# haasoscope_pro_power_board_-_5V.net
KiCad netlist of a schematic drawn in EAGLE
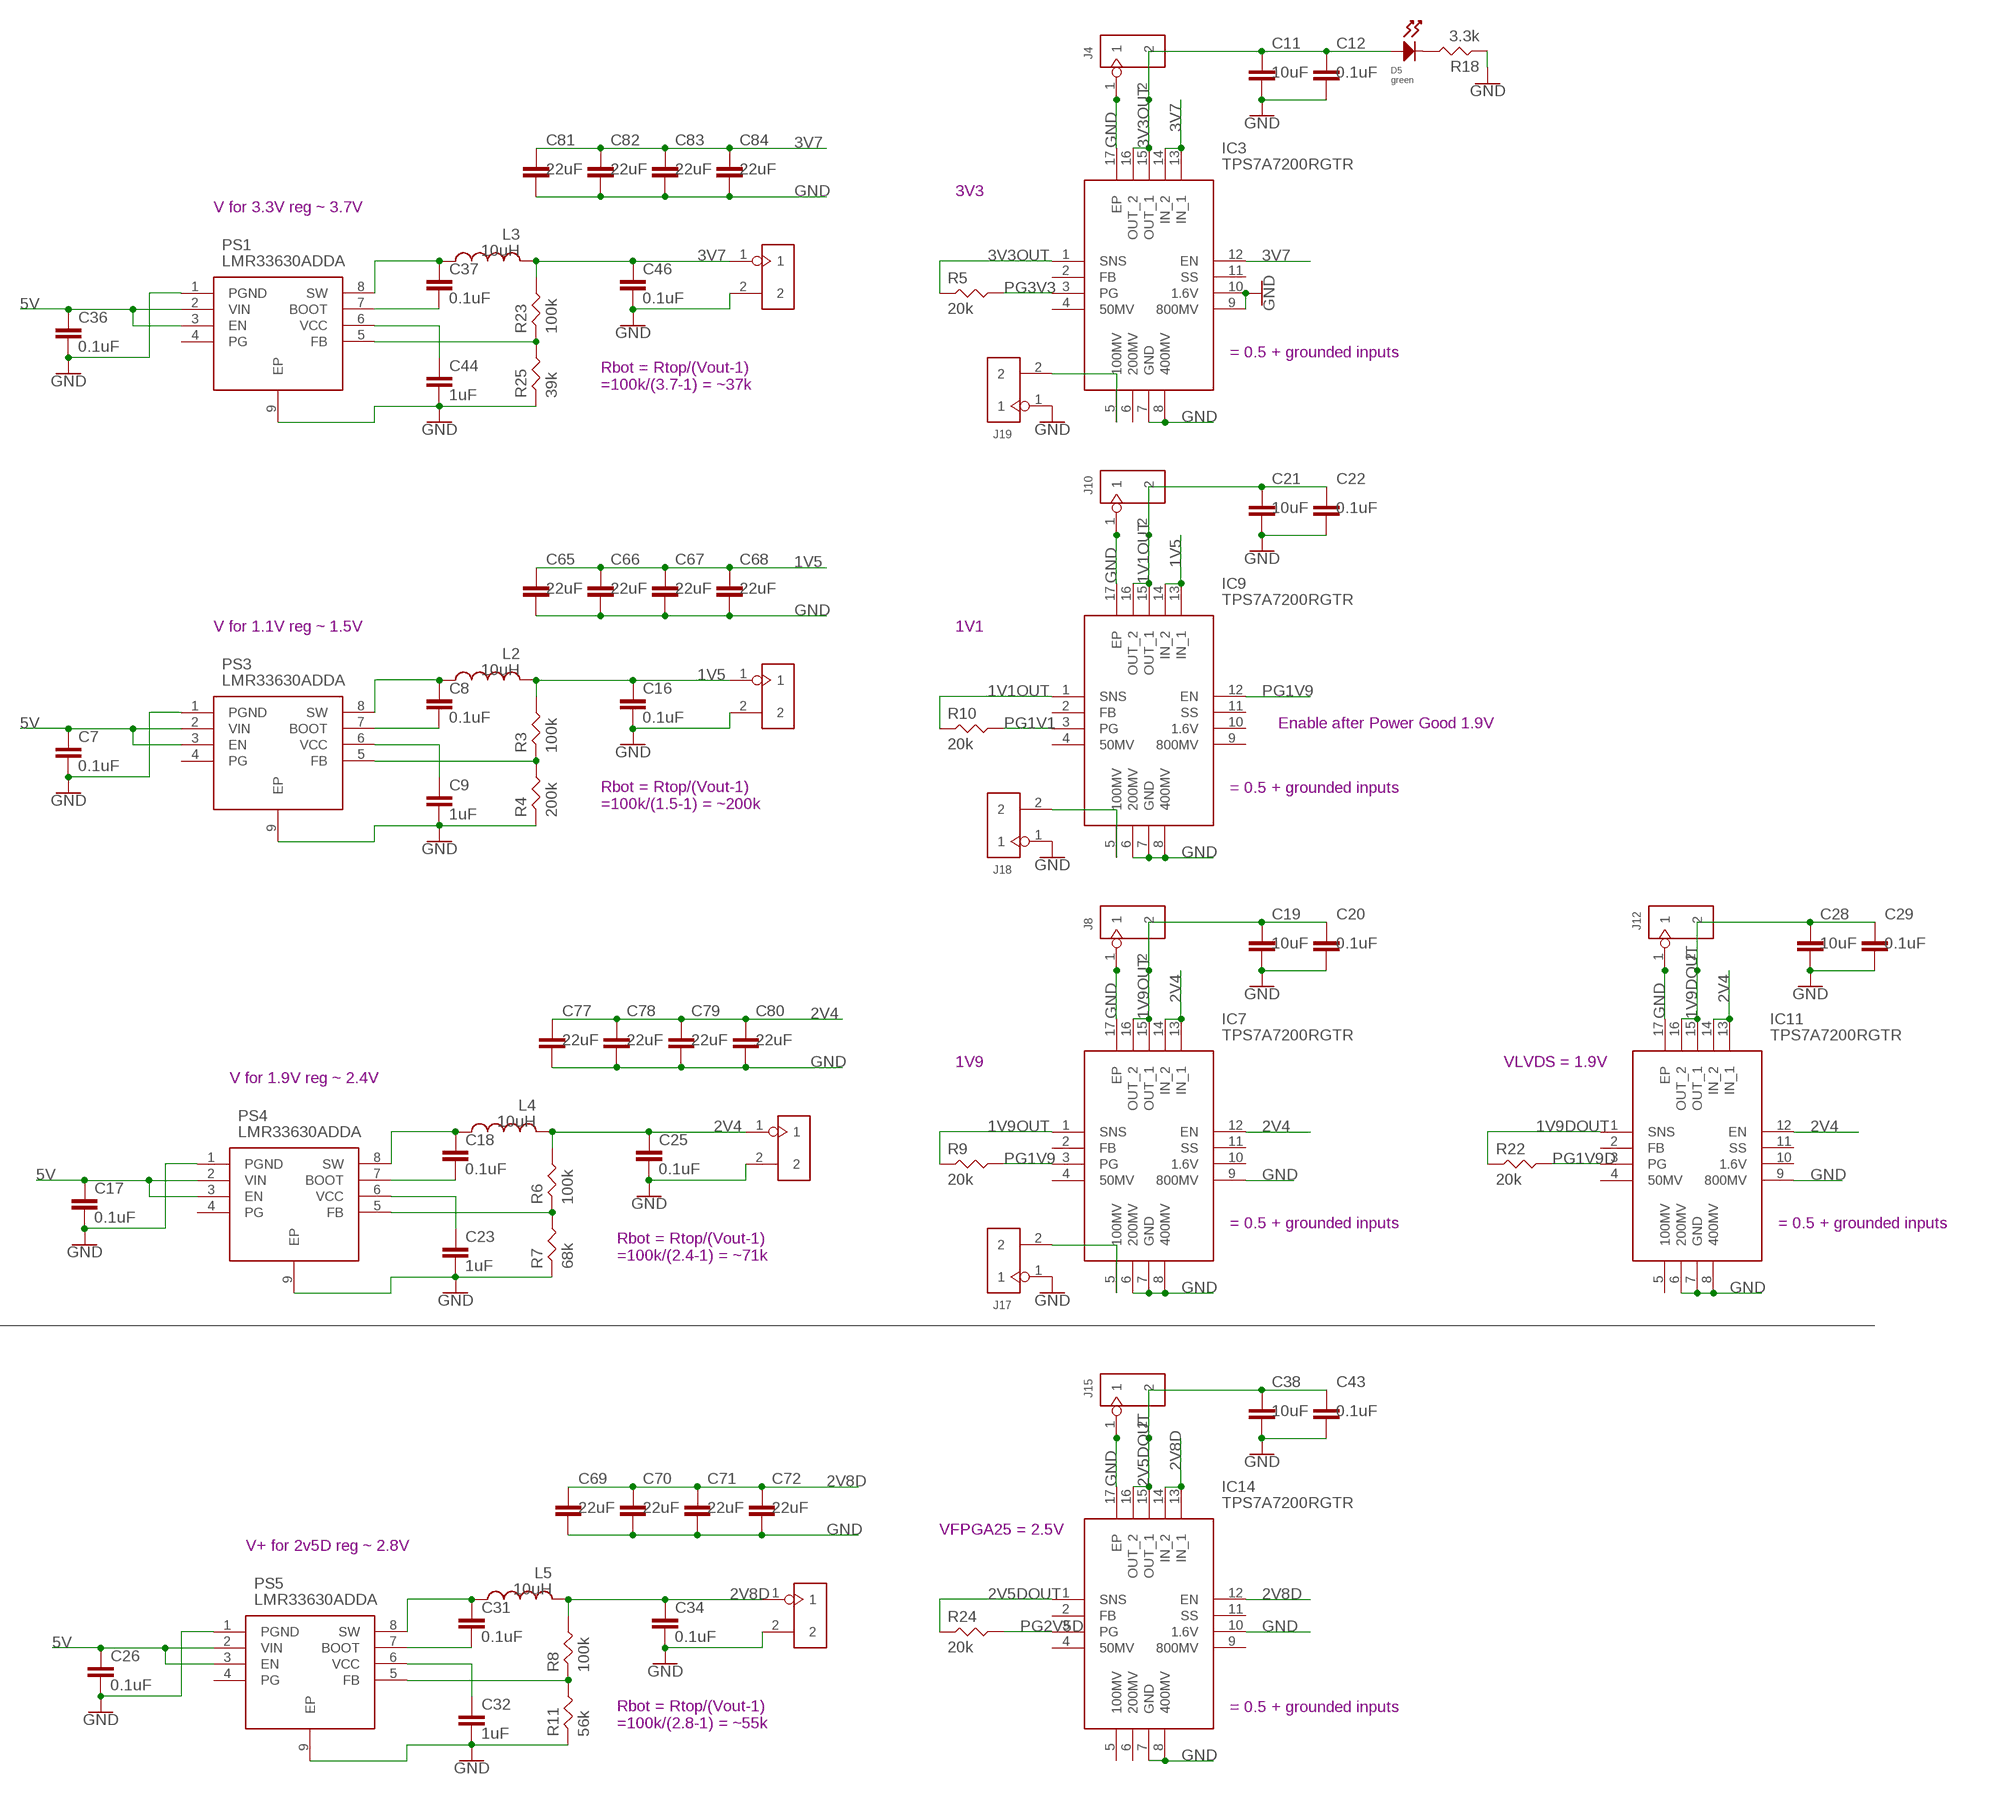
[diagram p0: schematic, sheet 1, part 1 of 2]
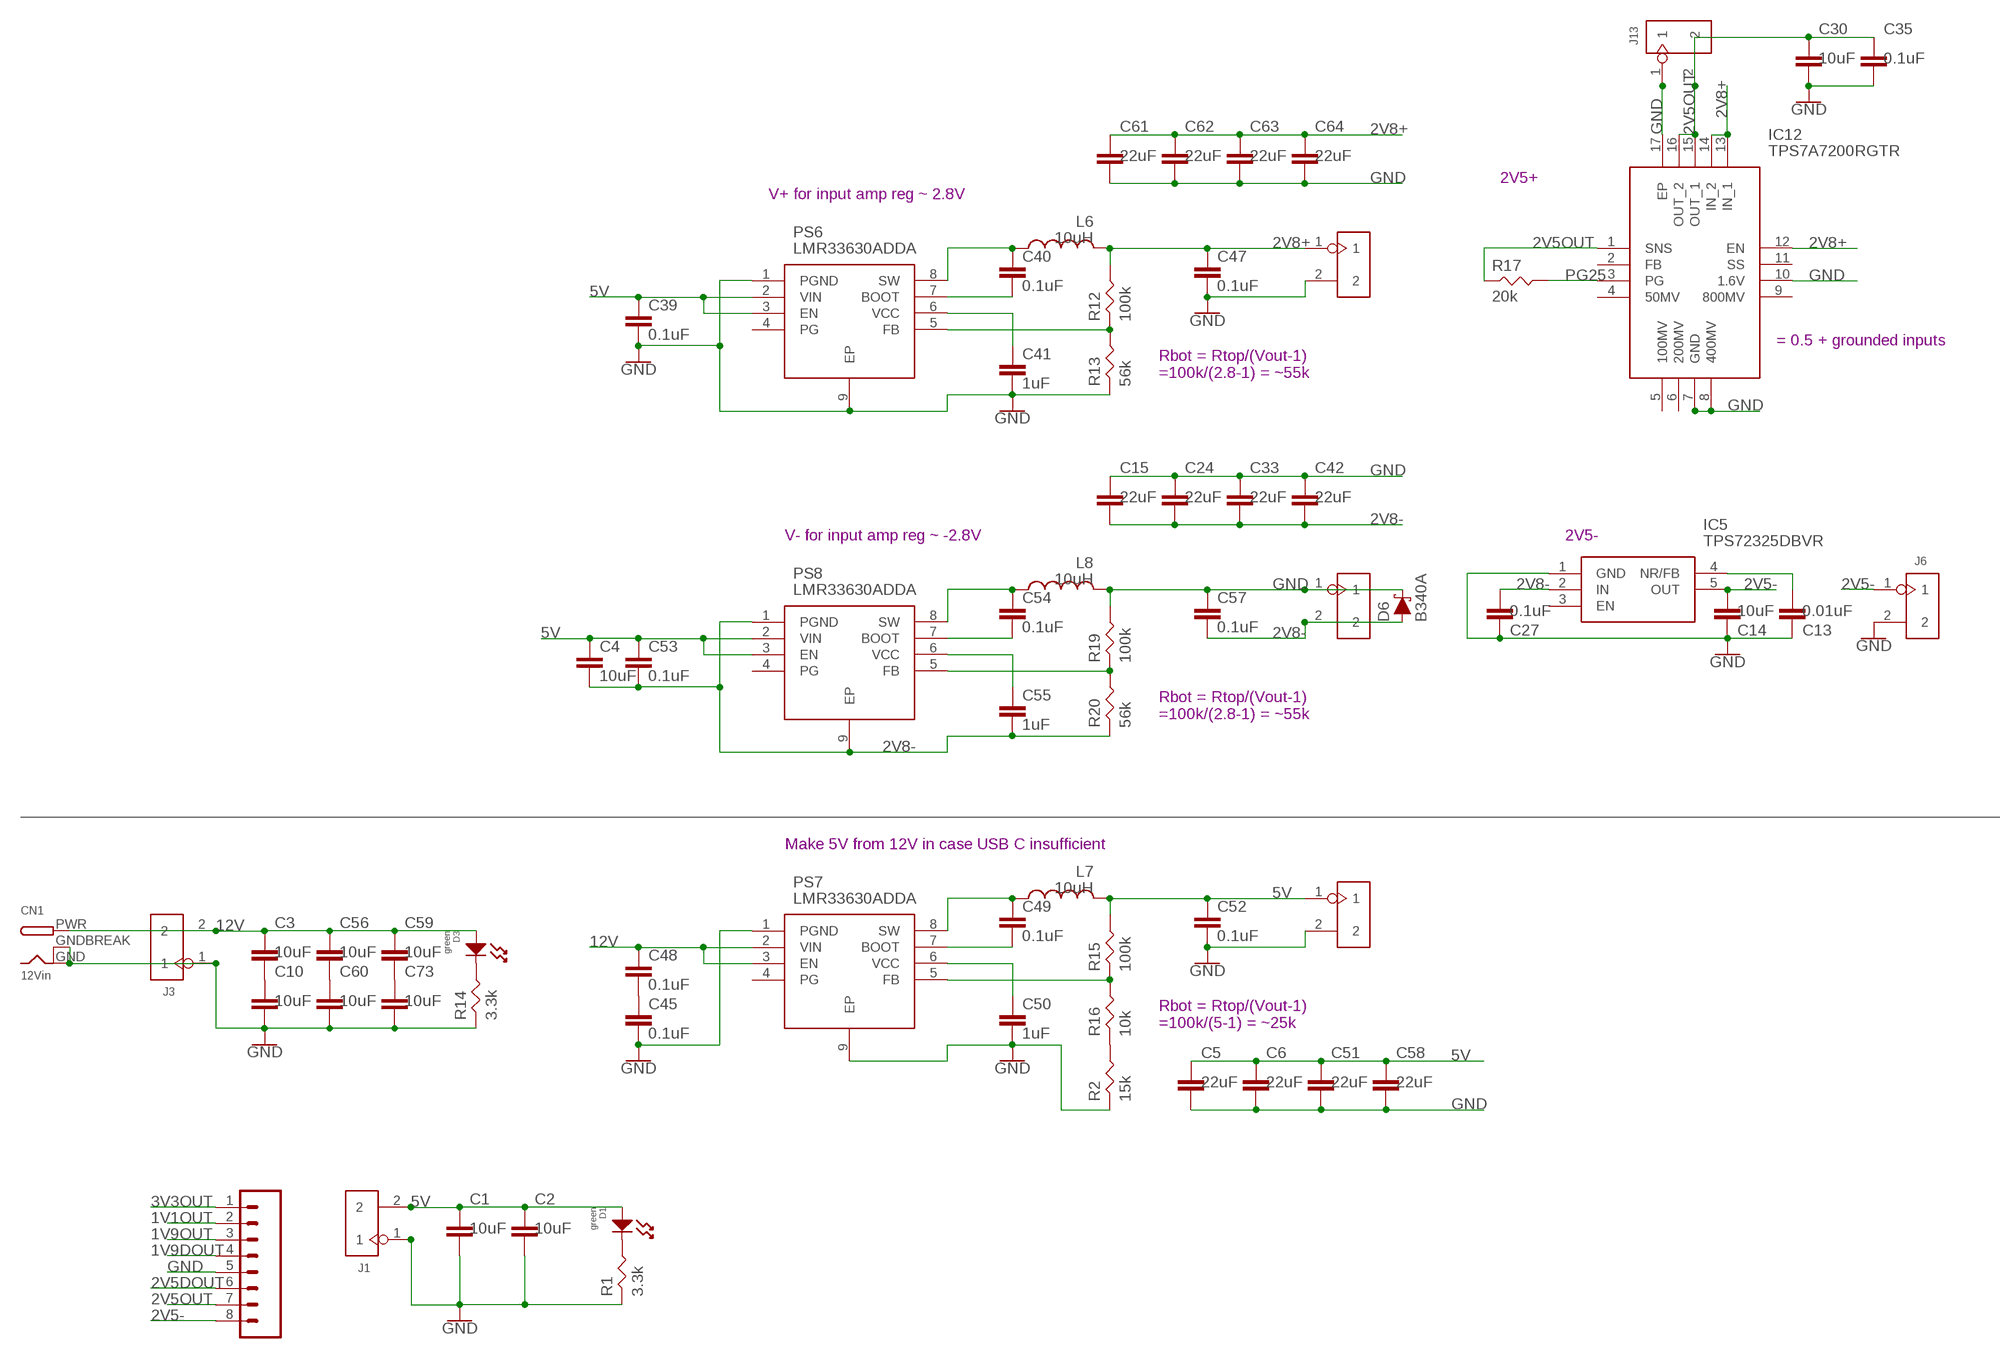
[diagram p1: schematic, sheet 1, part 2 of 2]

(export (version "E")
  (design (tool "Eeschema 10.0.6"))
  (components
    (comp (ref "C1")
      (value "10uF")
      (footprint "eagle-import:RESC0805_N")
      (libsource (lib "eagle-import") (part "CAPACITOR_0805_N"))
    )
    (comp (ref "C2")
      (value "10uF")
      (footprint "eagle-import:RESC0805_N")
      (libsource (lib "eagle-import") (part "CAPACITOR_0805_N"))
    )
    (comp (ref "C3")
      (value "10uF")
      (footprint "eagle-import:RESC0805_N")
      (libsource (lib "eagle-import") (part "CAPACITOR_0805_N"))
    )
    (comp (ref "C4")
      (value "10uF")
      (footprint "eagle-import:RESC0805_N")
      (libsource (lib "eagle-import") (part "CAPACITOR_0805_N"))
    )
    (comp (ref "C5")
      (value "22uF")
      (footprint "eagle-import:RESC0805_N")
      (libsource (lib "eagle-import") (part "CAPACITOR_0805_N"))
    )
    (comp (ref "C6")
      (value "22uF")
      (footprint "eagle-import:RESC0805_N")
      (libsource (lib "eagle-import") (part "CAPACITOR_0805_N"))
    )
    (comp (ref "C7")
      (value "0.1uF")
      (footprint "eagle-import:RESC0402_N")
      (libsource (lib "eagle-import") (part "CAPACITOR_0402_N"))
    )
    (comp (ref "C8")
      (value "0.1uF")
      (footprint "eagle-import:RESC0402_N")
      (libsource (lib "eagle-import") (part "CAPACITOR_0402_N"))
    )
    (comp (ref "C9")
      (value "1uF")
      (footprint "eagle-import:RESC0402_N")
      (libsource (lib "eagle-import") (part "CAPACITOR_0402_N"))
    )
    (comp (ref "C10")
      (value "10uF")
      (footprint "eagle-import:RESC0805_N")
      (libsource (lib "eagle-import") (part "CAPACITOR_0805_N"))
    )
    (comp (ref "C11")
      (value "10uF")
      (footprint "eagle-import:RESC0805_N")
      (libsource (lib "eagle-import") (part "CAPACITOR_0805_N"))
    )
    (comp (ref "C12")
      (value "0.1uF")
      (footprint "eagle-import:RESC0402_N")
      (libsource (lib "eagle-import") (part "CAPACITOR_0402_N"))
    )
    (comp (ref "C13")
      (value "0.01uF")
      (footprint "eagle-import:RESC0402_N")
      (libsource (lib "eagle-import") (part "CAPACITOR_0402_N"))
    )
    (comp (ref "C14")
      (value "10uF")
      (footprint "eagle-import:RESC0805_N")
      (libsource (lib "eagle-import") (part "CAPACITOR_0805_N"))
    )
    (comp (ref "C15")
      (value "22uF")
      (footprint "eagle-import:RESC0805_N")
      (libsource (lib "eagle-import") (part "CAPACITOR_0805_N"))
    )
    (comp (ref "C16")
      (value "0.1uF")
      (footprint "eagle-import:RESC0402_N")
      (libsource (lib "eagle-import") (part "CAPACITOR_0402_N"))
    )
    (comp (ref "C17")
      (value "0.1uF")
      (footprint "eagle-import:RESC0402_N")
      (libsource (lib "eagle-import") (part "CAPACITOR_0402_N"))
    )
    (comp (ref "C18")
      (value "0.1uF")
      (footprint "eagle-import:RESC0402_N")
      (libsource (lib "eagle-import") (part "CAPACITOR_0402_N"))
    )
    (comp (ref "C19")
      (value "10uF")
      (footprint "eagle-import:RESC0805_N")
      (libsource (lib "eagle-import") (part "CAPACITOR_0805_N"))
    )
    (comp (ref "C20")
      (value "0.1uF")
      (footprint "eagle-import:RESC0402_N")
      (libsource (lib "eagle-import") (part "CAPACITOR_0402_N"))
    )
    (comp (ref "C21")
      (value "10uF")
      (footprint "eagle-import:RESC0805_N")
      (libsource (lib "eagle-import") (part "CAPACITOR_0805_N"))
    )
    (comp (ref "C22")
      (value "0.1uF")
      (footprint "eagle-import:RESC0402_N")
      (libsource (lib "eagle-import") (part "CAPACITOR_0402_N"))
    )
    (comp (ref "C23")
      (value "1uF")
      (footprint "eagle-import:RESC0402_N")
      (libsource (lib "eagle-import") (part "CAPACITOR_0402_N"))
    )
    (comp (ref "C24")
      (value "22uF")
      (footprint "eagle-import:RESC0805_N")
      (libsource (lib "eagle-import") (part "CAPACITOR_0805_N"))
    )
    (comp (ref "C25")
      (value "0.1uF")
      (footprint "eagle-import:RESC0402_N")
      (libsource (lib "eagle-import") (part "CAPACITOR_0402_N"))
    )
    (comp (ref "C26")
      (value "0.1uF")
      (footprint "eagle-import:RESC0402_N")
      (libsource (lib "eagle-import") (part "CAPACITOR_0402_N"))
    )
    (comp (ref "C27")
      (value "0.1uF")
      (footprint "eagle-import:RESC0402_N")
      (libsource (lib "eagle-import") (part "CAPACITOR_0402_N"))
    )
    (comp (ref "C28")
      (value "10uF")
      (footprint "eagle-import:RESC0805_N")
      (libsource (lib "eagle-import") (part "CAPACITOR_0805_N"))
    )
    (comp (ref "C29")
      (value "0.1uF")
      (footprint "eagle-import:RESC0402_N")
      (libsource (lib "eagle-import") (part "CAPACITOR_0402_N"))
    )
    (comp (ref "C30")
      (value "10uF")
      (footprint "eagle-import:RESC0805_N")
      (libsource (lib "eagle-import") (part "CAPACITOR_0805_N"))
    )
    (comp (ref "C31")
      (value "0.1uF")
      (footprint "eagle-import:RESC0402_N")
      (libsource (lib "eagle-import") (part "CAPACITOR_0402_N"))
    )
    (comp (ref "C32")
      (value "1uF")
      (footprint "eagle-import:RESC0402_N")
      (libsource (lib "eagle-import") (part "CAPACITOR_0402_N"))
    )
    (comp (ref "C33")
      (value "22uF")
      (footprint "eagle-import:RESC0805_N")
      (libsource (lib "eagle-import") (part "CAPACITOR_0805_N"))
    )
    (comp (ref "C34")
      (value "0.1uF")
      (footprint "eagle-import:RESC0402_N")
      (libsource (lib "eagle-import") (part "CAPACITOR_0402_N"))
    )
    (comp (ref "C35")
      (value "0.1uF")
      (footprint "eagle-import:RESC0402_N")
      (libsource (lib "eagle-import") (part "CAPACITOR_0402_N"))
    )
    (comp (ref "C36")
      (value "0.1uF")
      (footprint "eagle-import:RESC0402_N")
      (libsource (lib "eagle-import") (part "CAPACITOR_0402_N"))
    )
    (comp (ref "C37")
      (value "0.1uF")
      (footprint "eagle-import:RESC0402_N")
      (libsource (lib "eagle-import") (part "CAPACITOR_0402_N"))
    )
    (comp (ref "C38")
      (value "10uF")
      (footprint "eagle-import:RESC0805_N")
      (libsource (lib "eagle-import") (part "CAPACITOR_0805_N"))
    )
    (comp (ref "C39")
      (value "0.1uF")
      (footprint "eagle-import:RESC0402_N")
      (libsource (lib "eagle-import") (part "CAPACITOR_0402_N"))
    )
    (comp (ref "C40")
      (value "0.1uF")
      (footprint "eagle-import:RESC0402_N")
      (libsource (lib "eagle-import") (part "CAPACITOR_0402_N"))
    )
    (comp (ref "C41")
      (value "1uF")
      (footprint "eagle-import:RESC0402_N")
      (libsource (lib "eagle-import") (part "CAPACITOR_0402_N"))
    )
    (comp (ref "C42")
      (value "22uF")
      (footprint "eagle-import:RESC0805_N")
      (libsource (lib "eagle-import") (part "CAPACITOR_0805_N"))
    )
    (comp (ref "C43")
      (value "0.1uF")
      (footprint "eagle-import:RESC0402_N")
      (libsource (lib "eagle-import") (part "CAPACITOR_0402_N"))
    )
    (comp (ref "C44")
      (value "1uF")
      (footprint "eagle-import:RESC0402_N")
      (libsource (lib "eagle-import") (part "CAPACITOR_0402_N"))
    )
    (comp (ref "C45")
      (value "0.1uF")
      (footprint "eagle-import:RESC0402_N")
      (libsource (lib "eagle-import") (part "CAPACITOR_0402_N"))
    )
    (comp (ref "C46")
      (value "0.1uF")
      (footprint "eagle-import:RESC0402_N")
      (libsource (lib "eagle-import") (part "CAPACITOR_0402_N"))
    )
    (comp (ref "C47")
      (value "0.1uF")
      (footprint "eagle-import:RESC0402_N")
      (libsource (lib "eagle-import") (part "CAPACITOR_0402_N"))
    )
    (comp (ref "C48")
      (value "0.1uF")
      (footprint "eagle-import:RESC0402_N")
      (libsource (lib "eagle-import") (part "CAPACITOR_0402_N"))
    )
    (comp (ref "C49")
      (value "0.1uF")
      (footprint "eagle-import:RESC0402_N")
      (libsource (lib "eagle-import") (part "CAPACITOR_0402_N"))
    )
    (comp (ref "C50")
      (value "1uF")
      (footprint "eagle-import:RESC0402_N")
      (libsource (lib "eagle-import") (part "CAPACITOR_0402_N"))
    )
    (comp (ref "C51")
      (value "22uF")
      (footprint "eagle-import:RESC0805_N")
      (libsource (lib "eagle-import") (part "CAPACITOR_0805_N"))
    )
    (comp (ref "C52")
      (value "0.1uF")
      (footprint "eagle-import:RESC0402_N")
      (libsource (lib "eagle-import") (part "CAPACITOR_0402_N"))
    )
    (comp (ref "C53")
      (value "0.1uF")
      (footprint "eagle-import:RESC0402_N")
      (libsource (lib "eagle-import") (part "CAPACITOR_0402_N"))
    )
    (comp (ref "C54")
      (value "0.1uF")
      (footprint "eagle-import:RESC0402_N")
      (libsource (lib "eagle-import") (part "CAPACITOR_0402_N"))
    )
    (comp (ref "C55")
      (value "1uF")
      (footprint "eagle-import:RESC0402_N")
      (libsource (lib "eagle-import") (part "CAPACITOR_0402_N"))
    )
    (comp (ref "C56")
      (value "10uF")
      (footprint "eagle-import:RESC0805_N")
      (libsource (lib "eagle-import") (part "CAPACITOR_0805_N"))
    )
    (comp (ref "C57")
      (value "0.1uF")
      (footprint "eagle-import:RESC0402_N")
      (libsource (lib "eagle-import") (part "CAPACITOR_0402_N"))
    )
    (comp (ref "C58")
      (value "22uF")
      (footprint "eagle-import:RESC0805_N")
      (libsource (lib "eagle-import") (part "CAPACITOR_0805_N"))
    )
    (comp (ref "C59")
      (value "10uF")
      (footprint "eagle-import:RESC0805_N")
      (libsource (lib "eagle-import") (part "CAPACITOR_0805_N"))
    )
    (comp (ref "C60")
      (value "10uF")
      (footprint "eagle-import:RESC0805_N")
      (libsource (lib "eagle-import") (part "CAPACITOR_0805_N"))
    )
    (comp (ref "C61")
      (value "22uF")
      (footprint "eagle-import:RESC0805_N")
      (libsource (lib "eagle-import") (part "CAPACITOR_0805_N"))
    )
    (comp (ref "C62")
      (value "22uF")
      (footprint "eagle-import:RESC0805_N")
      (libsource (lib "eagle-import") (part "CAPACITOR_0805_N"))
    )
    (comp (ref "C63")
      (value "22uF")
      (footprint "eagle-import:RESC0805_N")
      (libsource (lib "eagle-import") (part "CAPACITOR_0805_N"))
    )
    (comp (ref "C64")
      (value "22uF")
      (footprint "eagle-import:RESC0805_N")
      (libsource (lib "eagle-import") (part "CAPACITOR_0805_N"))
    )
    (comp (ref "C65")
      (value "22uF")
      (footprint "eagle-import:RESC0805_N")
      (libsource (lib "eagle-import") (part "CAPACITOR_0805_N"))
    )
    (comp (ref "C66")
      (value "22uF")
      (footprint "eagle-import:RESC0805_N")
      (libsource (lib "eagle-import") (part "CAPACITOR_0805_N"))
    )
    (comp (ref "C67")
      (value "22uF")
      (footprint "eagle-import:RESC0805_N")
      (libsource (lib "eagle-import") (part "CAPACITOR_0805_N"))
    )
    (comp (ref "C68")
      (value "22uF")
      (footprint "eagle-import:RESC0805_N")
      (libsource (lib "eagle-import") (part "CAPACITOR_0805_N"))
    )
    (comp (ref "C69")
      (value "22uF")
      (footprint "eagle-import:RESC0805_N")
      (libsource (lib "eagle-import") (part "CAPACITOR_0805_N"))
    )
    (comp (ref "C70")
      (value "22uF")
      (footprint "eagle-import:RESC0805_N")
      (libsource (lib "eagle-import") (part "CAPACITOR_0805_N"))
    )
    (comp (ref "C71")
      (value "22uF")
      (footprint "eagle-import:RESC0805_N")
      (libsource (lib "eagle-import") (part "CAPACITOR_0805_N"))
    )
    (comp (ref "C72")
      (value "22uF")
      (footprint "eagle-import:RESC0805_N")
      (libsource (lib "eagle-import") (part "CAPACITOR_0805_N"))
    )
    (comp (ref "C73")
      (value "10uF")
      (footprint "eagle-import:RESC0805_N")
      (libsource (lib "eagle-import") (part "CAPACITOR_0805_N"))
    )
    (comp (ref "C77")
      (value "22uF")
      (footprint "eagle-import:RESC0805_N")
      (libsource (lib "eagle-import") (part "CAPACITOR_0805_N"))
    )
    (comp (ref "C78")
      (value "22uF")
      (footprint "eagle-import:RESC0805_N")
      (libsource (lib "eagle-import") (part "CAPACITOR_0805_N"))
    )
    (comp (ref "C79")
      (value "22uF")
      (footprint "eagle-import:RESC0805_N")
      (libsource (lib "eagle-import") (part "CAPACITOR_0805_N"))
    )
    (comp (ref "C80")
      (value "22uF")
      (footprint "eagle-import:RESC0805_N")
      (libsource (lib "eagle-import") (part "CAPACITOR_0805_N"))
    )
    (comp (ref "C81")
      (value "22uF")
      (footprint "eagle-import:RESC0805_N")
      (libsource (lib "eagle-import") (part "CAPACITOR_0805_N"))
    )
    (comp (ref "C82")
      (value "22uF")
      (footprint "eagle-import:RESC0805_N")
      (libsource (lib "eagle-import") (part "CAPACITOR_0805_N"))
    )
    (comp (ref "C83")
      (value "22uF")
      (footprint "eagle-import:RESC0805_N")
      (libsource (lib "eagle-import") (part "CAPACITOR_0805_N"))
    )
    (comp (ref "C84")
      (value "22uF")
      (footprint "eagle-import:RESC0805_N")
      (libsource (lib "eagle-import") (part "CAPACITOR_0805_N"))
    )
    (comp (ref "CN1")
      (value "12Vin")
      (footprint "eagle-import:DCJACK_2MM_PTH")
      (libsource (lib "eagle-import") (part "DCBARRELPTH"))
    )
    (comp (ref "D1")
      (value "green")
      (footprint "eagle-import:LED0805")
      (fields (field (name "HOUSEPART") "NO"))
      (libsource (lib "eagle-import") (part "LED_SINGLE-0805"))
    )
    (comp (ref "D3")
      (value "green")
      (footprint "eagle-import:LED0805")
      (fields (field (name "HOUSEPART") "NO"))
      (libsource (lib "eagle-import") (part "LED_SINGLE-0805"))
    )
    (comp (ref "D5")
      (value "green")
      (footprint "eagle-import:LED0805")
      (fields (field (name "HOUSEPART") "NO"))
      (libsource (lib "eagle-import") (part "LED_SINGLE-0805"))
    )
    (comp (ref "D6")
      (value "B340A")
      (footprint "eagle-import:SMA-DIODE")
      (libsource (lib "eagle-import") (part "DIODE-SCHOTTKY-B340A"))
    )
    (comp (ref "IC3")
      (value "TPS7A7200RGTR")
      (footprint "eagle-import:QFN50P300X300X100-17N")
      (fields (field (name "MOUSER_PART_NUMBER") "595-TPS7A7200RGTR"))
      (libsource (lib "eagle-import") (part "TPS7A7200RGTR"))
    )
    (comp (ref "IC5")
      (value "TPS72325DBVR")
      (footprint "eagle-import:SOT95P280X145-5N")
      (fields (field (name "MOUSER_PART_NUMBER") "595-TPS72325DBVR"))
      (libsource (lib "eagle-import") (part "TPS72325DBVR"))
    )
    (comp (ref "IC7")
      (value "TPS7A7200RGTR")
      (footprint "eagle-import:QFN50P300X300X100-17N")
      (fields (field (name "MOUSER_PART_NUMBER") "595-TPS7A7200RGTR"))
      (libsource (lib "eagle-import") (part "TPS7A7200RGTR"))
    )
    (comp (ref "IC9")
      (value "TPS7A7200RGTR")
      (footprint "eagle-import:QFN50P300X300X100-17N")
      (fields (field (name "MOUSER_PART_NUMBER") "595-TPS7A7200RGTR"))
      (libsource (lib "eagle-import") (part "TPS7A7200RGTR"))
    )
    (comp (ref "IC11")
      (value "TPS7A7200RGTR")
      (footprint "eagle-import:QFN50P300X300X100-17N")
      (fields (field (name "MOUSER_PART_NUMBER") "595-TPS7A7200RGTR"))
      (libsource (lib "eagle-import") (part "TPS7A7200RGTR"))
    )
    (comp (ref "IC12")
      (value "TPS7A7200RGTR")
      (footprint "eagle-import:QFN50P300X300X100-17N")
      (fields (field (name "MOUSER_PART_NUMBER") "595-TPS7A7200RGTR"))
      (libsource (lib "eagle-import") (part "TPS7A7200RGTR"))
    )
    (comp (ref "IC14")
      (value "TPS7A7200RGTR")
      (footprint "eagle-import:QFN50P300X300X100-17N")
      (fields (field (name "MOUSER_PART_NUMBER") "595-TPS7A7200RGTR"))
      (libsource (lib "eagle-import") (part "TPS7A7200RGTR"))
    )
    (comp (ref "J1")
      (value "2p-2.54")
      (footprint "eagle-import:H2-2.54")
      (fields (field (name "MPN") "P125-1102A0BS116A1"))
      (libsource (lib "eagle-import") (part "DIP-BLACK-MALE-HEADER-VERT(2P-2.54)"))
    )
    (comp (ref "J2")
      (value "2p-2.54")
      (footprint "eagle-import:H2-2.54")
      (fields (field (name "MPN") "P125-1102A0BS116A1"))
      (libsource (lib "eagle-import") (part "DIP-BLACK-MALE-HEADER-VERT(2P-2.54)"))
    )
    (comp (ref "J3")
      (value "2p-2.54")
      (footprint "eagle-import:H2-2.54")
      (fields (field (name "MPN") "P125-1102A0BS116A1"))
      (libsource (lib "eagle-import") (part "DIP-BLACK-MALE-HEADER-VERT(2P-2.54)"))
    )
    (comp (ref "J4")
      (value "2p-2.54")
      (footprint "eagle-import:H2-2.54")
      (fields (field (name "MPN") "P125-1102A0BS116A1"))
      (libsource (lib "eagle-import") (part "DIP-BLACK-MALE-HEADER-VERT(2P-2.54)"))
    )
    (comp (ref "J5")
      (value "2p-2.54")
      (footprint "eagle-import:H2-2.54")
      (fields (field (name "MPN") "P125-1102A0BS116A1"))
      (libsource (lib "eagle-import") (part "DIP-BLACK-MALE-HEADER-VERT(2P-2.54)"))
    )
    (comp (ref "J6")
      (value "2p-2.54")
      (footprint "eagle-import:H2-2.54")
      (fields (field (name "MPN") "P125-1102A0BS116A1"))
      (libsource (lib "eagle-import") (part "DIP-BLACK-MALE-HEADER-VERT(2P-2.54)"))
    )
    (comp (ref "J7")
      (value "2p-2.54")
      (footprint "eagle-import:H2-2.54")
      (fields (field (name "MPN") "P125-1102A0BS116A1"))
      (libsource (lib "eagle-import") (part "DIP-BLACK-MALE-HEADER-VERT(2P-2.54)"))
    )
    (comp (ref "J8")
      (value "2p-2.54")
      (footprint "eagle-import:H2-2.54")
      (fields (field (name "MPN") "P125-1102A0BS116A1"))
      (libsource (lib "eagle-import") (part "DIP-BLACK-MALE-HEADER-VERT(2P-2.54)"))
    )
    (comp (ref "J9")
      (value "2p-2.54")
      (footprint "eagle-import:H2-2.54")
      (fields (field (name "MPN") "P125-1102A0BS116A1"))
      (libsource (lib "eagle-import") (part "DIP-BLACK-MALE-HEADER-VERT(2P-2.54)"))
    )
    (comp (ref "J10")
      (value "2p-2.54")
      (footprint "eagle-import:H2-2.54")
      (fields (field (name "MPN") "P125-1102A0BS116A1"))
      (libsource (lib "eagle-import") (part "DIP-BLACK-MALE-HEADER-VERT(2P-2.54)"))
    )
    (comp (ref "J11")
      (value "2p-2.54")
      (footprint "eagle-import:H2-2.54")
      (fields (field (name "MPN") "P125-1102A0BS116A1"))
      (libsource (lib "eagle-import") (part "DIP-BLACK-MALE-HEADER-VERT(2P-2.54)"))
    )
    (comp (ref "J12")
      (value "2p-2.54")
      (footprint "eagle-import:H2-2.54")
      (fields (field (name "MPN") "P125-1102A0BS116A1"))
      (libsource (lib "eagle-import") (part "DIP-BLACK-MALE-HEADER-VERT(2P-2.54)"))
    )
    (comp (ref "J13")
      (value "2p-2.54")
      (footprint "eagle-import:H2-2.54")
      (fields (field (name "MPN") "P125-1102A0BS116A1"))
      (libsource (lib "eagle-import") (part "DIP-BLACK-MALE-HEADER-VERT(2P-2.54)"))
    )
    (comp (ref "J14")
      (value "2p-2.54")
      (footprint "eagle-import:H2-2.54")
      (fields (field (name "MPN") "P125-1102A0BS116A1"))
      (libsource (lib "eagle-import") (part "DIP-BLACK-MALE-HEADER-VERT(2P-2.54)"))
    )
    (comp (ref "J15")
      (value "2p-2.54")
      (footprint "eagle-import:H2-2.54")
      (fields (field (name "MPN") "P125-1102A0BS116A1"))
      (libsource (lib "eagle-import") (part "DIP-BLACK-MALE-HEADER-VERT(2P-2.54)"))
    )
    (comp (ref "J16")
      (value "8pin")
      (footprint "eagle-import:1X08")
      (libsource (lib "eagle-import") (part "CONN_08{dblquote}"))
    )
    (comp (ref "J17")
      (value "2p-2.54")
      (footprint "eagle-import:H2-2.54")
      (fields (field (name "MPN") "P125-1102A0BS116A1"))
      (libsource (lib "eagle-import") (part "DIP-BLACK-MALE-HEADER-VERT(2P-2.54)"))
    )
    (comp (ref "J18")
      (value "2p-2.54")
      (footprint "eagle-import:H2-2.54")
      (fields (field (name "MPN") "P125-1102A0BS116A1"))
      (libsource (lib "eagle-import") (part "DIP-BLACK-MALE-HEADER-VERT(2P-2.54)"))
    )
    (comp (ref "J19")
      (value "2p-2.54")
      (footprint "eagle-import:H2-2.54")
      (fields (field (name "MPN") "P125-1102A0BS116A1"))
      (libsource (lib "eagle-import") (part "DIP-BLACK-MALE-HEADER-VERT(2P-2.54)"))
    )
    (comp (ref "J20")
      (value "2p-2.54")
      (footprint "eagle-import:H2-2.54")
      (fields (field (name "MPN") "P125-1102A0BS116A1"))
      (libsource (lib "eagle-import") (part "DIP-BLACK-MALE-HEADER-VERT(2P-2.54)"))
    )
    (comp (ref "L2")
      (value "10uH")
      (footprint "eagle-import:CDRH125")
      (libsource (lib "eagle-import") (part "INDUCTORPWR"))
    )
    (comp (ref "L3")
      (value "10uH")
      (footprint "eagle-import:CDRH125")
      (libsource (lib "eagle-import") (part "INDUCTORPWR"))
    )
    (comp (ref "L4")
      (value "10uH")
      (footprint "eagle-import:CDRH125")
      (libsource (lib "eagle-import") (part "INDUCTORPWR"))
    )
    (comp (ref "L5")
      (value "10uH")
      (footprint "eagle-import:CDRH125")
      (libsource (lib "eagle-import") (part "INDUCTORPWR"))
    )
    (comp (ref "L6")
      (value "10uH")
      (footprint "eagle-import:CDRH125")
      (libsource (lib "eagle-import") (part "INDUCTORPWR"))
    )
    (comp (ref "L7")
      (value "10uH")
      (footprint "eagle-import:CDRH125")
      (libsource (lib "eagle-import") (part "INDUCTORPWR"))
    )
    (comp (ref "L8")
      (value "10uH")
      (footprint "eagle-import:CDRH125")
      (libsource (lib "eagle-import") (part "INDUCTORPWR"))
    )
    (comp (ref "PS1")
      (value "LMR33630ADDA")
      (footprint "eagle-import:SOIC127P600X170-9N")
      (fields (field (name "MOUSER_PART_NUMBER") "595-LMR33630ADDA"))
      (libsource (lib "eagle-import") (part "LMR33630ADDA"))
    )
    (comp (ref "PS3")
      (value "LMR33630ADDA")
      (footprint "eagle-import:SOIC127P600X170-9N")
      (fields (field (name "MOUSER_PART_NUMBER") "595-LMR33630ADDA"))
      (libsource (lib "eagle-import") (part "LMR33630ADDA"))
    )
    (comp (ref "PS4")
      (value "LMR33630ADDA")
      (footprint "eagle-import:SOIC127P600X170-9N")
      (fields (field (name "MOUSER_PART_NUMBER") "595-LMR33630ADDA"))
      (libsource (lib "eagle-import") (part "LMR33630ADDA"))
    )
    (comp (ref "PS5")
      (value "LMR33630ADDA")
      (footprint "eagle-import:SOIC127P600X170-9N")
      (fields (field (name "MOUSER_PART_NUMBER") "595-LMR33630ADDA"))
      (libsource (lib "eagle-import") (part "LMR33630ADDA"))
    )
    (comp (ref "PS6")
      (value "LMR33630ADDA")
      (footprint "eagle-import:SOIC127P600X170-9N")
      (fields (field (name "MOUSER_PART_NUMBER") "595-LMR33630ADDA"))
      (libsource (lib "eagle-import") (part "LMR33630ADDA"))
    )
    (comp (ref "PS7")
      (value "LMR33630ADDA")
      (footprint "eagle-import:SOIC127P600X170-9N")
      (fields (field (name "MOUSER_PART_NUMBER") "595-LMR33630ADDA"))
      (libsource (lib "eagle-import") (part "LMR33630ADDA"))
    )
    (comp (ref "PS8")
      (value "LMR33630ADDA")
      (footprint "eagle-import:SOIC127P600X170-9N")
      (fields (field (name "MOUSER_PART_NUMBER") "595-LMR33630ADDA"))
      (libsource (lib "eagle-import") (part "LMR33630ADDA"))
    )
    (comp (ref "R1")
      (value "3.3k")
      (footprint "eagle-import:RES-0402")
      (libsource (lib "eagle-import") (part "RES-0402"))
    )
    (comp (ref "R2")
      (value "15k")
      (footprint "eagle-import:RES-0402")
      (libsource (lib "eagle-import") (part "RES-0402"))
    )
    (comp (ref "R3")
      (value "100k")
      (footprint "eagle-import:RES-0402")
      (libsource (lib "eagle-import") (part "RES-0402"))
    )
    (comp (ref "R4")
      (value "200k")
      (footprint "eagle-import:RES-0402")
      (libsource (lib "eagle-import") (part "RES-0402"))
    )
    (comp (ref "R5")
      (value "20k")
      (footprint "eagle-import:RES-0402")
      (libsource (lib "eagle-import") (part "RES-0402"))
    )
    (comp (ref "R6")
      (value "100k")
      (footprint "eagle-import:RES-0402")
      (libsource (lib "eagle-import") (part "RES-0402"))
    )
    (comp (ref "R7")
      (value "68k")
      (footprint "eagle-import:RES-0402")
      (libsource (lib "eagle-import") (part "RES-0402"))
    )
    (comp (ref "R8")
      (value "100k")
      (footprint "eagle-import:RES-0402")
      (libsource (lib "eagle-import") (part "RES-0402"))
    )
    (comp (ref "R9")
      (value "20k")
      (footprint "eagle-import:RES-0402")
      (libsource (lib "eagle-import") (part "RES-0402"))
    )
    (comp (ref "R10")
      (value "20k")
      (footprint "eagle-import:RES-0402")
      (libsource (lib "eagle-import") (part "RES-0402"))
    )
    (comp (ref "R11")
      (value "56k")
      (footprint "eagle-import:RES-0402")
      (libsource (lib "eagle-import") (part "RES-0402"))
    )
    (comp (ref "R12")
      (value "100k")
      (footprint "eagle-import:RES-0402")
      (libsource (lib "eagle-import") (part "RES-0402"))
    )
    (comp (ref "R13")
      (value "56k")
      (footprint "eagle-import:RES-0402")
      (libsource (lib "eagle-import") (part "RES-0402"))
    )
    (comp (ref "R14")
      (value "3.3k")
      (footprint "eagle-import:RES-0402")
      (libsource (lib "eagle-import") (part "RES-0402"))
    )
    (comp (ref "R15")
      (value "100k")
      (footprint "eagle-import:RES-0402")
      (libsource (lib "eagle-import") (part "RES-0402"))
    )
    (comp (ref "R16")
      (value "10k")
      (footprint "eagle-import:RES-0402")
      (libsource (lib "eagle-import") (part "RES-0402"))
    )
    (comp (ref "R17")
      (value "20k")
      (footprint "eagle-import:RES-0402")
      (libsource (lib "eagle-import") (part "RES-0402"))
    )
    (comp (ref "R18")
      (value "3.3k")
      (footprint "eagle-import:RES-0402")
      (libsource (lib "eagle-import") (part "RES-0402"))
    )
    (comp (ref "R19")
      (value "100k")
      (footprint "eagle-import:RES-0402")
      (libsource (lib "eagle-import") (part "RES-0402"))
    )
    (comp (ref "R20")
      (value "56k")
      (footprint "eagle-import:RES-0402")
      (libsource (lib "eagle-import") (part "RES-0402"))
    )
    (comp (ref "R22")
      (value "20k")
      (footprint "eagle-import:RES-0402")
      (libsource (lib "eagle-import") (part "RES-0402"))
    )
    (comp (ref "R23")
      (value "100k")
      (footprint "eagle-import:RES-0402")
      (libsource (lib "eagle-import") (part "RES-0402"))
    )
    (comp (ref "R24")
      (value "20k")
      (footprint "eagle-import:RES-0402")
      (libsource (lib "eagle-import") (part "RES-0402"))
    )
    (comp (ref "R25")
      (value "39k")
      (footprint "eagle-import:RES-0402")
      (libsource (lib "eagle-import") (part "RES-0402"))
    )
  )
  (nets
    (net (code "1") (name "/1V1OUT") (class "Default")
      (node (ref "C21") (pin "1") (pinfunction "1_1") (pintype "passive"))
      (node (ref "C22") (pin "1") (pinfunction "1_1") (pintype "passive"))
      (node (ref "IC9") (pin "1") (pinfunction "SNS_1") (pintype "bidirectional"))
      (node (ref "IC9") (pin "15") (pinfunction "OUT_1_15") (pintype "bidirectional"))
      (node (ref "IC9") (pin "16") (pinfunction "OUT_2_16") (pintype "bidirectional"))
      (node (ref "J10") (pin "2") (pinfunction "2_2") (pintype "bidirectional"))
      (node (ref "J16") (pin "2") (pinfunction "2_2") (pintype "passive"))
      (node (ref "R10") (pin "P$1") (pinfunction "P$1_P$1") (pintype "bidirectional"))
    )
    (net (code "2") (name "/1V5") (class "Default")
      (node (ref "C16") (pin "1") (pinfunction "1_1") (pintype "passive"))
      (node (ref "C65") (pin "1") (pinfunction "1_1") (pintype "passive"))
      (node (ref "C66") (pin "1") (pinfunction "1_1") (pintype "passive"))
      (node (ref "C67") (pin "1") (pinfunction "1_1") (pintype "passive"))
      (node (ref "C68") (pin "1") (pinfunction "1_1") (pintype "passive"))
      (node (ref "IC9") (pin "13") (pinfunction "IN_1_13") (pintype "bidirectional"))
      (node (ref "IC9") (pin "14") (pinfunction "IN_2_14") (pintype "bidirectional"))
      (node (ref "J2") (pin "1") (pinfunction "1_1") (pintype "bidirectional"))
      (node (ref "L2") (pin "2") (pinfunction "2_2") (pintype "passive"))
      (node (ref "R3") (pin "P$2") (pinfunction "P$2_P$2") (pintype "bidirectional"))
    )
    (net (code "3") (name "/1V9DOUT") (class "Default")
      (node (ref "C28") (pin "1") (pinfunction "1_1") (pintype "passive"))
      (node (ref "C29") (pin "1") (pinfunction "1_1") (pintype "passive"))
      (node (ref "IC11") (pin "1") (pinfunction "SNS_1") (pintype "bidirectional"))
      (node (ref "IC11") (pin "15") (pinfunction "OUT_1_15") (pintype "bidirectional"))
      (node (ref "IC11") (pin "16") (pinfunction "OUT_2_16") (pintype "bidirectional"))
      (node (ref "J12") (pin "2") (pinfunction "2_2") (pintype "bidirectional"))
      (node (ref "J16") (pin "4") (pinfunction "4_4") (pintype "passive"))
      (node (ref "R22") (pin "P$1") (pinfunction "P$1_P$1") (pintype "bidirectional"))
    )
    (net (code "4") (name "/1V9OUT") (class "Default")
      (node (ref "C19") (pin "1") (pinfunction "1_1") (pintype "passive"))
      (node (ref "C20") (pin "1") (pinfunction "1_1") (pintype "passive"))
      (node (ref "IC7") (pin "1") (pinfunction "SNS_1") (pintype "bidirectional"))
      (node (ref "IC7") (pin "15") (pinfunction "OUT_1_15") (pintype "bidirectional"))
      (node (ref "IC7") (pin "16") (pinfunction "OUT_2_16") (pintype "bidirectional"))
      (node (ref "J16") (pin "3") (pinfunction "3_3") (pintype "passive"))
      (node (ref "J8") (pin "2") (pinfunction "2_2") (pintype "bidirectional"))
      (node (ref "R9") (pin "P$1") (pinfunction "P$1_P$1") (pintype "bidirectional"))
    )
    (net (code "5") (name "/2V4") (class "Default")
      (node (ref "C25") (pin "1") (pinfunction "1_1") (pintype "passive"))
      (node (ref "C77") (pin "1") (pinfunction "1_1") (pintype "passive"))
      (node (ref "C78") (pin "1") (pinfunction "1_1") (pintype "passive"))
      (node (ref "C79") (pin "1") (pinfunction "1_1") (pintype "passive"))
      (node (ref "C80") (pin "1") (pinfunction "1_1") (pintype "passive"))
      (node (ref "IC11") (pin "12") (pinfunction "EN_12") (pintype "bidirectional"))
      (node (ref "IC11") (pin "13") (pinfunction "IN_1_13") (pintype "bidirectional"))
      (node (ref "IC11") (pin "14") (pinfunction "IN_2_14") (pintype "bidirectional"))
      (node (ref "IC7") (pin "12") (pinfunction "EN_12") (pintype "bidirectional"))
      (node (ref "IC7") (pin "13") (pinfunction "IN_1_13") (pintype "bidirectional"))
      (node (ref "IC7") (pin "14") (pinfunction "IN_2_14") (pintype "bidirectional"))
      (node (ref "J5") (pin "1") (pinfunction "1_1") (pintype "bidirectional"))
      (node (ref "L4") (pin "2") (pinfunction "2_2") (pintype "passive"))
      (node (ref "R6") (pin "P$2") (pinfunction "P$2_P$2") (pintype "bidirectional"))
    )
    (net (code "6") (name "/2V5-") (class "Default")
      (node (ref "C14") (pin "1") (pinfunction "1_1") (pintype "passive"))
      (node (ref "IC5") (pin "5") (pinfunction "OUT_5") (pintype "bidirectional"))
      (node (ref "J16") (pin "8") (pinfunction "8_8") (pintype "passive"))
      (node (ref "J6") (pin "1") (pinfunction "1_1") (pintype "bidirectional"))
    )
    (net (code "7") (name "/2V5DOUT") (class "Default")
      (node (ref "C38") (pin "1") (pinfunction "1_1") (pintype "passive"))
      (node (ref "C43") (pin "1") (pinfunction "1_1") (pintype "passive"))
      (node (ref "IC14") (pin "1") (pinfunction "SNS_1") (pintype "bidirectional"))
      (node (ref "IC14") (pin "15") (pinfunction "OUT_1_15") (pintype "bidirectional"))
      (node (ref "IC14") (pin "16") (pinfunction "OUT_2_16") (pintype "bidirectional"))
      (node (ref "J15") (pin "2") (pinfunction "2_2") (pintype "bidirectional"))
      (node (ref "J16") (pin "6") (pinfunction "6_6") (pintype "passive"))
      (node (ref "R24") (pin "P$1") (pinfunction "P$1_P$1") (pintype "bidirectional"))
    )
    (net (code "8") (name "/2V5OUT") (class "Default")
      (node (ref "C30") (pin "1") (pinfunction "1_1") (pintype "passive"))
      (node (ref "C35") (pin "1") (pinfunction "1_1") (pintype "passive"))
      (node (ref "IC12") (pin "1") (pinfunction "SNS_1") (pintype "bidirectional"))
      (node (ref "IC12") (pin "15") (pinfunction "OUT_1_15") (pintype "bidirectional"))
      (node (ref "IC12") (pin "16") (pinfunction "OUT_2_16") (pintype "bidirectional"))
      (node (ref "J13") (pin "2") (pinfunction "2_2") (pintype "bidirectional"))
      (node (ref "J16") (pin "7") (pinfunction "7_7") (pintype "passive"))
      (node (ref "R17") (pin "P$1") (pinfunction "P$1_P$1") (pintype "bidirectional"))
    )
    (net (code "9") (name "/2V8+") (class "Default")
      (node (ref "C47") (pin "1") (pinfunction "1_1") (pintype "passive"))
      (node (ref "C61") (pin "1") (pinfunction "1_1") (pintype "passive"))
      (node (ref "C62") (pin "1") (pinfunction "1_1") (pintype "passive"))
      (node (ref "C63") (pin "1") (pinfunction "1_1") (pintype "passive"))
      (node (ref "C64") (pin "1") (pinfunction "1_1") (pintype "passive"))
      (node (ref "IC12") (pin "12") (pinfunction "EN_12") (pintype "bidirectional"))
      (node (ref "IC12") (pin "13") (pinfunction "IN_1_13") (pintype "bidirectional"))
      (node (ref "IC12") (pin "14") (pinfunction "IN_2_14") (pintype "bidirectional"))
      (node (ref "J9") (pin "1") (pinfunction "1_1") (pintype "bidirectional"))
      (node (ref "L6") (pin "2") (pinfunction "2_2") (pintype "passive"))
      (node (ref "R12") (pin "P$2") (pinfunction "P$2_P$2") (pintype "bidirectional"))
    )
    (net (code "10") (name "/2V8-") (class "Default")
      (node (ref "C15") (pin "2") (pinfunction "2_2") (pintype "passive"))
      (node (ref "C24") (pin "2") (pinfunction "2_2") (pintype "passive"))
      (node (ref "C27") (pin "1") (pinfunction "1_1") (pintype "passive"))
      (node (ref "C33") (pin "2") (pinfunction "2_2") (pintype "passive"))
      (node (ref "C4") (pin "2") (pinfunction "2_2") (pintype "passive"))
      (node (ref "C42") (pin "2") (pinfunction "2_2") (pintype "passive"))
      (node (ref "C53") (pin "2") (pinfunction "2_2") (pintype "passive"))
      (node (ref "C55") (pin "2") (pinfunction "2_2") (pintype "passive"))
      (node (ref "C57") (pin "2") (pinfunction "2_2") (pintype "passive"))
      (node (ref "D6") (pin "A") (pinfunction "A_A") (pintype "passive"))
      (node (ref "IC5") (pin "2") (pinfunction "IN_2") (pintype "bidirectional"))
      (node (ref "J20") (pin "2") (pinfunction "2_2") (pintype "bidirectional"))
      (node (ref "PS8") (pin "1") (pinfunction "PGND_1") (pintype "bidirectional"))
      (node (ref "PS8") (pin "9") (pinfunction "EP_9") (pintype "bidirectional"))
      (node (ref "R20") (pin "P$1") (pinfunction "P$1_P$1") (pintype "bidirectional"))
    )
    (net (code "11") (name "/2V8D") (class "Default")
      (node (ref "C34") (pin "1") (pinfunction "1_1") (pintype "passive"))
      (node (ref "C69") (pin "1") (pinfunction "1_1") (pintype "passive"))
      (node (ref "C70") (pin "1") (pinfunction "1_1") (pintype "passive"))
      (node (ref "C71") (pin "1") (pinfunction "1_1") (pintype "passive"))
      (node (ref "C72") (pin "1") (pinfunction "1_1") (pintype "passive"))
      (node (ref "IC14") (pin "12") (pinfunction "EN_12") (pintype "bidirectional"))
      (node (ref "IC14") (pin "13") (pinfunction "IN_1_13") (pintype "bidirectional"))
      (node (ref "IC14") (pin "14") (pinfunction "IN_2_14") (pintype "bidirectional"))
      (node (ref "J7") (pin "1") (pinfunction "1_1") (pintype "bidirectional"))
      (node (ref "L5") (pin "2") (pinfunction "2_2") (pintype "passive"))
      (node (ref "R8") (pin "P$2") (pinfunction "P$2_P$2") (pintype "bidirectional"))
    )
    (net (code "12") (name "/3V3OUT") (class "Default")
      (node (ref "C11") (pin "1") (pinfunction "1_1") (pintype "passive"))
      (node (ref "C12") (pin "1") (pinfunction "1_1") (pintype "passive"))
      (node (ref "D5") (pin "ANODE") (pinfunction "ANODE_ANODE") (pintype "power_in"))
      (node (ref "IC3") (pin "1") (pinfunction "SNS_1") (pintype "bidirectional"))
      (node (ref "IC3") (pin "15") (pinfunction "OUT_1_15") (pintype "bidirectional"))
      (node (ref "IC3") (pin "16") (pinfunction "OUT_2_16") (pintype "bidirectional"))
      (node (ref "J16") (pin "1") (pinfunction "1_1") (pintype "passive"))
      (node (ref "J4") (pin "2") (pinfunction "2_2") (pintype "bidirectional"))
      (node (ref "R5") (pin "P$1") (pinfunction "P$1_P$1") (pintype "bidirectional"))
    )
    (net (code "13") (name "/3V7") (class "Default")
      (node (ref "C46") (pin "1") (pinfunction "1_1") (pintype "passive"))
      (node (ref "C81") (pin "1") (pinfunction "1_1") (pintype "passive"))
      (node (ref "C82") (pin "1") (pinfunction "1_1") (pintype "passive"))
      (node (ref "C83") (pin "1") (pinfunction "1_1") (pintype "passive"))
      (node (ref "C84") (pin "1") (pinfunction "1_1") (pintype "passive"))
      (node (ref "IC3") (pin "12") (pinfunction "EN_12") (pintype "bidirectional"))
      (node (ref "IC3") (pin "13") (pinfunction "IN_1_13") (pintype "bidirectional"))
      (node (ref "IC3") (pin "14") (pinfunction "IN_2_14") (pintype "bidirectional"))
      (node (ref "J14") (pin "1") (pinfunction "1_1") (pintype "bidirectional"))
      (node (ref "L3") (pin "2") (pinfunction "2_2") (pintype "passive"))
      (node (ref "R23") (pin "P$2") (pinfunction "P$2_P$2") (pintype "bidirectional"))
    )
    (net (code "14") (name "/5V") (class "Default")
      (node (ref "C1") (pin "1") (pinfunction "1_1") (pintype "passive"))
      (node (ref "C17") (pin "1") (pinfunction "1_1") (pintype "passive"))
      (node (ref "C2") (pin "1") (pinfunction "1_1") (pintype "passive"))
      (node (ref "C26") (pin "1") (pinfunction "1_1") (pintype "passive"))
      (node (ref "C36") (pin "1") (pinfunction "1_1") (pintype "passive"))
      (node (ref "C39") (pin "1") (pinfunction "1_1") (pintype "passive"))
      (node (ref "C4") (pin "1") (pinfunction "1_1") (pintype "passive"))
      (node (ref "C5") (pin "1") (pinfunction "1_1") (pintype "passive"))
      (node (ref "C51") (pin "1") (pinfunction "1_1") (pintype "passive"))
      (node (ref "C52") (pin "1") (pinfunction "1_1") (pintype "passive"))
      (node (ref "C53") (pin "1") (pinfunction "1_1") (pintype "passive"))
      (node (ref "C58") (pin "1") (pinfunction "1_1") (pintype "passive"))
      (node (ref "C6") (pin "1") (pinfunction "1_1") (pintype "passive"))
      (node (ref "C7") (pin "1") (pinfunction "1_1") (pintype "passive"))
      (node (ref "D1") (pin "ANODE") (pinfunction "ANODE_ANODE") (pintype "power_in"))
      (node (ref "J1") (pin "2") (pinfunction "2_2") (pintype "bidirectional"))
      (node (ref "J11") (pin "1") (pinfunction "1_1") (pintype "bidirectional"))
      (node (ref "L7") (pin "2") (pinfunction "2_2") (pintype "passive"))
      (node (ref "PS1") (pin "2") (pinfunction "VIN_2") (pintype "bidirectional"))
      (node (ref "PS1") (pin "3") (pinfunction "EN_3") (pintype "bidirectional"))
      (node (ref "PS3") (pin "2") (pinfunction "VIN_2") (pintype "bidirectional"))
      (node (ref "PS3") (pin "3") (pinfunction "EN_3") (pintype "bidirectional"))
      (node (ref "PS4") (pin "2") (pinfunction "VIN_2") (pintype "bidirectional"))
      (node (ref "PS4") (pin "3") (pinfunction "EN_3") (pintype "bidirectional"))
      (node (ref "PS5") (pin "2") (pinfunction "VIN_2") (pintype "bidirectional"))
      (node (ref "PS5") (pin "3") (pinfunction "EN_3") (pintype "bidirectional"))
      (node (ref "PS6") (pin "2") (pinfunction "VIN_2") (pintype "bidirectional"))
      (node (ref "PS6") (pin "3") (pinfunction "EN_3") (pintype "bidirectional"))
      (node (ref "PS8") (pin "2") (pinfunction "VIN_2") (pintype "bidirectional"))
      (node (ref "PS8") (pin "3") (pinfunction "EN_3") (pintype "bidirectional"))
      (node (ref "R15") (pin "P$2") (pinfunction "P$2_P$2") (pintype "bidirectional"))
    )
    (net (code "15") (name "/12V") (class "Default")
      (node (ref "C3") (pin "1") (pinfunction "1_1") (pintype "passive"))
      (node (ref "C48") (pin "1") (pinfunction "1_1") (pintype "passive"))
      (node (ref "C56") (pin "1") (pinfunction "1_1") (pintype "passive"))
      (node (ref "C59") (pin "1") (pinfunction "1_1") (pintype "passive"))
      (node (ref "CN1") (pin "PWR") (pinfunction "PWR_PWR") (pintype "power_in"))
      (node (ref "D3") (pin "ANODE") (pinfunction "ANODE_ANODE") (pintype "power_in"))
      (node (ref "J3") (pin "2") (pinfunction "2_2") (pintype "bidirectional"))
      (node (ref "PS7") (pin "2") (pinfunction "VIN_2") (pintype "bidirectional"))
      (node (ref "PS7") (pin "3") (pinfunction "EN_3") (pintype "bidirectional"))
    )
    (net (code "16") (name "/PG1V1") (class "Default")
      (node (ref "IC9") (pin "3") (pinfunction "PG_3") (pintype "bidirectional"))
      (node (ref "R10") (pin "P$2") (pinfunction "P$2_P$2") (pintype "bidirectional"))
    )
    (net (code "17") (name "/PG1V9") (class "Default")
      (node (ref "IC7") (pin "3") (pinfunction "PG_3") (pintype "bidirectional"))
      (node (ref "IC9") (pin "12") (pinfunction "EN_12") (pintype "bidirectional"))
      (node (ref "R9") (pin "P$2") (pinfunction "P$2_P$2") (pintype "bidirectional"))
    )
    (net (code "18") (name "/PG1V9D") (class "Default")
      (node (ref "IC11") (pin "3") (pinfunction "PG_3") (pintype "bidirectional"))
      (node (ref "R22") (pin "P$2") (pinfunction "P$2_P$2") (pintype "bidirectional"))
    )
    (net (code "19") (name "/PG2V5D") (class "Default")
      (node (ref "IC14") (pin "3") (pinfunction "PG_3") (pintype "bidirectional"))
      (node (ref "R24") (pin "P$2") (pinfunction "P$2_P$2") (pintype "bidirectional"))
    )
    (net (code "20") (name "/PG3V3") (class "Default")
      (node (ref "IC3") (pin "3") (pinfunction "PG_3") (pintype "bidirectional"))
      (node (ref "R5") (pin "P$2") (pinfunction "P$2_P$2") (pintype "bidirectional"))
    )
    (net (code "21") (name "/PG25") (class "Default")
      (node (ref "IC12") (pin "3") (pinfunction "PG_3") (pintype "bidirectional"))
      (node (ref "R17") (pin "P$2") (pinfunction "P$2_P$2") (pintype "bidirectional"))
    )
    (net (code "22") (name "GND") (class "Default")
      (node (ref "C1") (pin "2") (pinfunction "2_2") (pintype "passive"))
      (node (ref "C10") (pin "2") (pinfunction "2_2") (pintype "passive"))
      (node (ref "C11") (pin "2") (pinfunction "2_2") (pintype "passive"))
      (node (ref "C12") (pin "2") (pinfunction "2_2") (pintype "passive"))
      (node (ref "C13") (pin "2") (pinfunction "2_2") (pintype "passive"))
      (node (ref "C14") (pin "2") (pinfunction "2_2") (pintype "passive"))
      (node (ref "C15") (pin "1") (pinfunction "1_1") (pintype "passive"))
      (node (ref "C16") (pin "2") (pinfunction "2_2") (pintype "passive"))
      (node (ref "C17") (pin "2") (pinfunction "2_2") (pintype "passive"))
      (node (ref "C19") (pin "2") (pinfunction "2_2") (pintype "passive"))
      (node (ref "C2") (pin "2") (pinfunction "2_2") (pintype "passive"))
      (node (ref "C20") (pin "2") (pinfunction "2_2") (pintype "passive"))
      (node (ref "C21") (pin "2") (pinfunction "2_2") (pintype "passive"))
      (node (ref "C22") (pin "2") (pinfunction "2_2") (pintype "passive"))
      (node (ref "C23") (pin "2") (pinfunction "2_2") (pintype "passive"))
      (node (ref "C24") (pin "1") (pinfunction "1_1") (pintype "passive"))
      (node (ref "C25") (pin "2") (pinfunction "2_2") (pintype "passive"))
      (node (ref "C26") (pin "2") (pinfunction "2_2") (pintype "passive"))
      (node (ref "C27") (pin "2") (pinfunction "2_2") (pintype "passive"))
      (node (ref "C28") (pin "2") (pinfunction "2_2") (pintype "passive"))
      (node (ref "C29") (pin "2") (pinfunction "2_2") (pintype "passive"))
      (node (ref "C30") (pin "2") (pinfunction "2_2") (pintype "passive"))
      (node (ref "C32") (pin "2") (pinfunction "2_2") (pintype "passive"))
      (node (ref "C33") (pin "1") (pinfunction "1_1") (pintype "passive"))
      (node (ref "C34") (pin "2") (pinfunction "2_2") (pintype "passive"))
      (node (ref "C35") (pin "2") (pinfunction "2_2") (pintype "passive"))
      (node (ref "C36") (pin "2") (pinfunction "2_2") (pintype "passive"))
      (node (ref "C38") (pin "2") (pinfunction "2_2") (pintype "passive"))
      (node (ref "C39") (pin "2") (pinfunction "2_2") (pintype "passive"))
      (node (ref "C41") (pin "2") (pinfunction "2_2") (pintype "passive"))
      (node (ref "C42") (pin "1") (pinfunction "1_1") (pintype "passive"))
      (node (ref "C43") (pin "2") (pinfunction "2_2") (pintype "passive"))
      (node (ref "C44") (pin "2") (pinfunction "2_2") (pintype "passive"))
      (node (ref "C45") (pin "2") (pinfunction "2_2") (pintype "passive"))
      (node (ref "C46") (pin "2") (pinfunction "2_2") (pintype "passive"))
      (node (ref "C47") (pin "2") (pinfunction "2_2") (pintype "passive"))
      (node (ref "C5") (pin "2") (pinfunction "2_2") (pintype "passive"))
      (node (ref "C50") (pin "2") (pinfunction "2_2") (pintype "passive"))
      (node (ref "C51") (pin "2") (pinfunction "2_2") (pintype "passive"))
      (node (ref "C52") (pin "2") (pinfunction "2_2") (pintype "passive"))
      (node (ref "C57") (pin "1") (pinfunction "1_1") (pintype "passive"))
      (node (ref "C58") (pin "2") (pinfunction "2_2") (pintype "passive"))
      (node (ref "C6") (pin "2") (pinfunction "2_2") (pintype "passive"))
      (node (ref "C60") (pin "2") (pinfunction "2_2") (pintype "passive"))
      (node (ref "C61") (pin "2") (pinfunction "2_2") (pintype "passive"))
      (node (ref "C62") (pin "2") (pinfunction "2_2") (pintype "passive"))
      (node (ref "C63") (pin "2") (pinfunction "2_2") (pintype "passive"))
      (node (ref "C64") (pin "2") (pinfunction "2_2") (pintype "passive"))
      (node (ref "C65") (pin "2") (pinfunction "2_2") (pintype "passive"))
      (node (ref "C66") (pin "2") (pinfunction "2_2") (pintype "passive"))
      (node (ref "C67") (pin "2") (pinfunction "2_2") (pintype "passive"))
      (node (ref "C68") (pin "2") (pinfunction "2_2") (pintype "passive"))
      (node (ref "C69") (pin "2") (pinfunction "2_2") (pintype "passive"))
      (node (ref "C7") (pin "2") (pinfunction "2_2") (pintype "passive"))
      (node (ref "C70") (pin "2") (pinfunction "2_2") (pintype "passive"))
      (node (ref "C71") (pin "2") (pinfunction "2_2") (pintype "passive"))
      (node (ref "C72") (pin "2") (pinfunction "2_2") (pintype "passive"))
      (node (ref "C73") (pin "2") (pinfunction "2_2") (pintype "passive"))
      (node (ref "C77") (pin "2") (pinfunction "2_2") (pintype "passive"))
      (node (ref "C78") (pin "2") (pinfunction "2_2") (pintype "passive"))
      (node (ref "C79") (pin "2") (pinfunction "2_2") (pintype "passive"))
      (node (ref "C80") (pin "2") (pinfunction "2_2") (pintype "passive"))
      (node (ref "C81") (pin "2") (pinfunction "2_2") (pintype "passive"))
      (node (ref "C82") (pin "2") (pinfunction "2_2") (pintype "passive"))
      (node (ref "C83") (pin "2") (pinfunction "2_2") (pintype "passive"))
      (node (ref "C84") (pin "2") (pinfunction "2_2") (pintype "passive"))
      (node (ref "C9") (pin "2") (pinfunction "2_2") (pintype "passive"))
      (node (ref "CN1") (pin "GND") (pinfunction "GND_GND") (pintype "power_in"))
      (node (ref "CN1") (pin "GNDBREAK") (pinfunction "GNDBREAK_GNDBREAK") (pintype "power_in"))
      (node (ref "D6") (pin "C") (pinfunction "C_C") (pintype "passive"))
      (node (ref "IC11") (pin "17") (pinfunction "EP_17") (pintype "bidirectional"))
      (node (ref "IC11") (pin "6") (pinfunction "200MV_6") (pintype "bidirectional"))
      (node (ref "IC11") (pin "7") (pinfunction "GND_7") (pintype "bidirectional"))
      (node (ref "IC11") (pin "8") (pinfunction "400MV_8") (pintype "bidirectional"))
      (node (ref "IC11") (pin "9") (pinfunction "800MV_9") (pintype "bidirectional"))
      (node (ref "IC12") (pin "10") (pinfunction "1.6V_10") (pintype "bidirectional"))
      (node (ref "IC12") (pin "17") (pinfunction "EP_17") (pintype "bidirectional"))
      (node (ref "IC12") (pin "7") (pinfunction "GND_7") (pintype "bidirectional"))
      (node (ref "IC12") (pin "8") (pinfunction "400MV_8") (pintype "bidirectional"))
      (node (ref "IC14") (pin "10") (pinfunction "1.6V_10") (pintype "bidirectional"))
      (node (ref "IC14") (pin "17") (pinfunction "EP_17") (pintype "bidirectional"))
      (node (ref "IC14") (pin "7") (pinfunction "GND_7") (pintype "bidirectional"))
      (node (ref "IC14") (pin "8") (pinfunction "400MV_8") (pintype "bidirectional"))
      (node (ref "IC3") (pin "10") (pinfunction "1.6V_10") (pintype "bidirectional"))
      (node (ref "IC3") (pin "17") (pinfunction "EP_17") (pintype "bidirectional"))
      (node (ref "IC3") (pin "7") (pinfunction "GND_7") (pintype "bidirectional"))
      (node (ref "IC3") (pin "8") (pinfunction "400MV_8") (pintype "bidirectional"))
      (node (ref "IC3") (pin "9") (pinfunction "800MV_9") (pintype "bidirectional"))
      (node (ref "IC5") (pin "1") (pinfunction "GND_1") (pintype "bidirectional"))
      (node (ref "IC7") (pin "17") (pinfunction "EP_17") (pintype "bidirectional"))
      (node (ref "IC7") (pin "6") (pinfunction "200MV_6") (pintype "bidirectional"))
      (node (ref "IC7") (pin "7") (pinfunction "GND_7") (pintype "bidirectional"))
      (node (ref "IC7") (pin "8") (pinfunction "400MV_8") (pintype "bidirectional"))
      (node (ref "IC7") (pin "9") (pinfunction "800MV_9") (pintype "bidirectional"))
      (node (ref "IC9") (pin "17") (pinfunction "EP_17") (pintype "bidirectional"))
      (node (ref "IC9") (pin "6") (pinfunction "200MV_6") (pintype "bidirectional"))
      (node (ref "IC9") (pin "7") (pinfunction "GND_7") (pintype "bidirectional"))
      (node (ref "IC9") (pin "8") (pinfunction "400MV_8") (pintype "bidirectional"))
      (node (ref "J1") (pin "1") (pinfunction "1_1") (pintype "bidirectional"))
      (node (ref "J10") (pin "1") (pinfunction "1_1") (pintype "bidirectional"))
      (node (ref "J11") (pin "2") (pinfunction "2_2") (pintype "bidirectional"))
      (node (ref "J12") (pin "1") (pinfunction "1_1") (pintype "bidirectional"))
      (node (ref "J13") (pin "1") (pinfunction "1_1") (pintype "bidirectional"))
      (node (ref "J14") (pin "2") (pinfunction "2_2") (pintype "bidirectional"))
      (node (ref "J15") (pin "1") (pinfunction "1_1") (pintype "bidirectional"))
      (node (ref "J16") (pin "5") (pinfunction "5_5") (pintype "passive"))
      (node (ref "J17") (pin "1") (pinfunction "1_1") (pintype "bidirectional"))
      (node (ref "J18") (pin "1") (pinfunction "1_1") (pintype "bidirectional"))
      (node (ref "J19") (pin "1") (pinfunction "1_1") (pintype "bidirectional"))
      (node (ref "J2") (pin "2") (pinfunction "2_2") (pintype "bidirectional"))
      (node (ref "J20") (pin "1") (pinfunction "1_1") (pintype "bidirectional"))
      (node (ref "J3") (pin "1") (pinfunction "1_1") (pintype "bidirectional"))
      (node (ref "J4") (pin "1") (pinfunction "1_1") (pintype "bidirectional"))
      (node (ref "J5") (pin "2") (pinfunction "2_2") (pintype "bidirectional"))
      (node (ref "J6") (pin "2") (pinfunction "2_2") (pintype "bidirectional"))
      (node (ref "J7") (pin "2") (pinfunction "2_2") (pintype "bidirectional"))
      (node (ref "J8") (pin "1") (pinfunction "1_1") (pintype "bidirectional"))
      (node (ref "J9") (pin "2") (pinfunction "2_2") (pintype "bidirectional"))
      (node (ref "L8") (pin "2") (pinfunction "2_2") (pintype "passive"))
      (node (ref "PS1") (pin "1") (pinfunction "PGND_1") (pintype "bidirectional"))
      (node (ref "PS1") (pin "9") (pinfunction "EP_9") (pintype "bidirectional"))
      (node (ref "PS3") (pin "1") (pinfunction "PGND_1") (pintype "bidirectional"))
      (node (ref "PS3") (pin "9") (pinfunction "EP_9") (pintype "bidirectional"))
      (node (ref "PS4") (pin "1") (pinfunction "PGND_1") (pintype "bidirectional"))
      (node (ref "PS4") (pin "9") (pinfunction "EP_9") (pintype "bidirectional"))
      (node (ref "PS5") (pin "1") (pinfunction "PGND_1") (pintype "bidirectional"))
      (node (ref "PS5") (pin "9") (pinfunction "EP_9") (pintype "bidirectional"))
      (node (ref "PS6") (pin "1") (pinfunction "PGND_1") (pintype "bidirectional"))
      (node (ref "PS6") (pin "9") (pinfunction "EP_9") (pintype "bidirectional"))
      (node (ref "PS7") (pin "1") (pinfunction "PGND_1") (pintype "bidirectional"))
      (node (ref "PS7") (pin "9") (pinfunction "EP_9") (pintype "bidirectional"))
      (node (ref "R1") (pin "P$1") (pinfunction "P$1_P$1") (pintype "bidirectional"))
      (node (ref "R11") (pin "P$1") (pinfunction "P$1_P$1") (pintype "bidirectional"))
      (node (ref "R13") (pin "P$1") (pinfunction "P$1_P$1") (pintype "bidirectional"))
      (node (ref "R14") (pin "P$1") (pinfunction "P$1_P$1") (pintype "bidirectional"))
      (node (ref "R18") (pin "P$1") (pinfunction "P$1_P$1") (pintype "bidirectional"))
      (node (ref "R19") (pin "P$2") (pinfunction "P$2_P$2") (pintype "bidirectional"))
      (node (ref "R2") (pin "P$1") (pinfunction "P$1_P$1") (pintype "bidirectional"))
      (node (ref "R25") (pin "P$1") (pinfunction "P$1_P$1") (pintype "bidirectional"))
      (node (ref "R4") (pin "P$1") (pinfunction "P$1_P$1") (pintype "bidirectional"))
      (node (ref "R7") (pin "P$1") (pinfunction "P$1_P$1") (pintype "bidirectional"))
    )
    (net (code "23") (name "Net-(C10-Pad1)") (class "Default")
      (node (ref "C10") (pin "1") (pinfunction "1_1") (pintype "passive"))
      (node (ref "C3") (pin "2") (pinfunction "2_2") (pintype "passive"))
    )
    (net (code "24") (name "Net-(C45-Pad1)") (class "Default")
      (node (ref "C45") (pin "1") (pinfunction "1_1") (pintype "passive"))
      (node (ref "C48") (pin "2") (pinfunction "2_2") (pintype "passive"))
    )
    (net (code "25") (name "Net-(C56-Pad2)") (class "Default")
      (node (ref "C56") (pin "2") (pinfunction "2_2") (pintype "passive"))
      (node (ref "C60") (pin "1") (pinfunction "1_1") (pintype "passive"))
    )
    (net (code "26") (name "Net-(C59-Pad2)") (class "Default")
      (node (ref "C59") (pin "2") (pinfunction "2_2") (pintype "passive"))
      (node (ref "C73") (pin "1") (pinfunction "1_1") (pintype "passive"))
    )
    (net (code "27") (name "Net-(D1-PadCATHODE)") (class "Default")
      (node (ref "D1") (pin "CATHODE") (pinfunction "CATHODE_CATHODE") (pintype "power_in"))
      (node (ref "R1") (pin "P$2") (pinfunction "P$2_P$2") (pintype "bidirectional"))
    )
    (net (code "28") (name "Net-(D3-PadCATHODE)") (class "Default")
      (node (ref "D3") (pin "CATHODE") (pinfunction "CATHODE_CATHODE") (pintype "power_in"))
      (node (ref "R14") (pin "P$2") (pinfunction "P$2_P$2") (pintype "bidirectional"))
    )
    (net (code "29") (name "Net-(D5-PadCATHODE)") (class "Default")
      (node (ref "D5") (pin "CATHODE") (pinfunction "CATHODE_CATHODE") (pintype "power_in"))
      (node (ref "R18") (pin "P$2") (pinfunction "P$2_P$2") (pintype "bidirectional"))
    )
    (net (code "30") (name "Net-(IC3-100MV)") (class "Default")
      (node (ref "IC3") (pin "5") (pinfunction "100MV_5") (pintype "bidirectional"))
      (node (ref "J19") (pin "2") (pinfunction "2_2") (pintype "bidirectional"))
    )
    (net (code "31") (name "Net-(IC5-NR{slash}FB)") (class "Default")
      (node (ref "C13") (pin "1") (pinfunction "1_1") (pintype "passive"))
      (node (ref "IC5") (pin "4") (pinfunction "NR/FB_4") (pintype "bidirectional"))
    )
    (net (code "32") (name "Net-(IC7-100MV)") (class "Default")
      (node (ref "IC7") (pin "5") (pinfunction "100MV_5") (pintype "bidirectional"))
      (node (ref "J17") (pin "2") (pinfunction "2_2") (pintype "bidirectional"))
    )
    (net (code "33") (name "Net-(IC9-100MV)") (class "Default")
      (node (ref "IC9") (pin "5") (pinfunction "100MV_5") (pintype "bidirectional"))
      (node (ref "J18") (pin "2") (pinfunction "2_2") (pintype "bidirectional"))
    )
    (net (code "34") (name "Net-(PS1-BOOT)") (class "Default")
      (node (ref "C37") (pin "2") (pinfunction "2_2") (pintype "passive"))
      (node (ref "PS1") (pin "7") (pinfunction "BOOT_7") (pintype "bidirectional"))
    )
    (net (code "35") (name "Net-(PS1-FB)") (class "Default")
      (node (ref "PS1") (pin "5") (pinfunction "FB_5") (pintype "bidirectional"))
      (node (ref "R23") (pin "P$1") (pinfunction "P$1_P$1") (pintype "bidirectional"))
      (node (ref "R25") (pin "P$2") (pinfunction "P$2_P$2") (pintype "bidirectional"))
    )
    (net (code "36") (name "Net-(PS1-SW)") (class "Default")
      (node (ref "C37") (pin "1") (pinfunction "1_1") (pintype "passive"))
      (node (ref "L3") (pin "1") (pinfunction "1_1") (pintype "passive"))
      (node (ref "PS1") (pin "8") (pinfunction "SW_8") (pintype "bidirectional"))
    )
    (net (code "37") (name "Net-(PS1-VCC)") (class "Default")
      (node (ref "C44") (pin "1") (pinfunction "1_1") (pintype "passive"))
      (node (ref "PS1") (pin "6") (pinfunction "VCC_6") (pintype "bidirectional"))
    )
    (net (code "38") (name "Net-(PS3-BOOT)") (class "Default")
      (node (ref "C8") (pin "2") (pinfunction "2_2") (pintype "passive"))
      (node (ref "PS3") (pin "7") (pinfunction "BOOT_7") (pintype "bidirectional"))
    )
    (net (code "39") (name "Net-(PS3-FB)") (class "Default")
      (node (ref "PS3") (pin "5") (pinfunction "FB_5") (pintype "bidirectional"))
      (node (ref "R3") (pin "P$1") (pinfunction "P$1_P$1") (pintype "bidirectional"))
      (node (ref "R4") (pin "P$2") (pinfunction "P$2_P$2") (pintype "bidirectional"))
    )
    (net (code "40") (name "Net-(PS3-SW)") (class "Default")
      (node (ref "C8") (pin "1") (pinfunction "1_1") (pintype "passive"))
      (node (ref "L2") (pin "1") (pinfunction "1_1") (pintype "passive"))
      (node (ref "PS3") (pin "8") (pinfunction "SW_8") (pintype "bidirectional"))
    )
    (net (code "41") (name "Net-(PS3-VCC)") (class "Default")
      (node (ref "C9") (pin "1") (pinfunction "1_1") (pintype "passive"))
      (node (ref "PS3") (pin "6") (pinfunction "VCC_6") (pintype "bidirectional"))
    )
    (net (code "42") (name "Net-(PS4-BOOT)") (class "Default")
      (node (ref "C18") (pin "2") (pinfunction "2_2") (pintype "passive"))
      (node (ref "PS4") (pin "7") (pinfunction "BOOT_7") (pintype "bidirectional"))
    )
    (net (code "43") (name "Net-(PS4-FB)") (class "Default")
      (node (ref "PS4") (pin "5") (pinfunction "FB_5") (pintype "bidirectional"))
      (node (ref "R6") (pin "P$1") (pinfunction "P$1_P$1") (pintype "bidirectional"))
      (node (ref "R7") (pin "P$2") (pinfunction "P$2_P$2") (pintype "bidirectional"))
    )
    (net (code "44") (name "Net-(PS4-SW)") (class "Default")
      (node (ref "C18") (pin "1") (pinfunction "1_1") (pintype "passive"))
      (node (ref "L4") (pin "1") (pinfunction "1_1") (pintype "passive"))
      (node (ref "PS4") (pin "8") (pinfunction "SW_8") (pintype "bidirectional"))
    )
    (net (code "45") (name "Net-(PS4-VCC)") (class "Default")
      (node (ref "C23") (pin "1") (pinfunction "1_1") (pintype "passive"))
      (node (ref "PS4") (pin "6") (pinfunction "VCC_6") (pintype "bidirectional"))
    )
    (net (code "46") (name "Net-(PS5-BOOT)") (class "Default")
      (node (ref "C31") (pin "2") (pinfunction "2_2") (pintype "passive"))
      (node (ref "PS5") (pin "7") (pinfunction "BOOT_7") (pintype "bidirectional"))
    )
    (net (code "47") (name "Net-(PS5-FB)") (class "Default")
      (node (ref "PS5") (pin "5") (pinfunction "FB_5") (pintype "bidirectional"))
      (node (ref "R11") (pin "P$2") (pinfunction "P$2_P$2") (pintype "bidirectional"))
      (node (ref "R8") (pin "P$1") (pinfunction "P$1_P$1") (pintype "bidirectional"))
    )
    (net (code "48") (name "Net-(PS5-SW)") (class "Default")
      (node (ref "C31") (pin "1") (pinfunction "1_1") (pintype "passive"))
      (node (ref "L5") (pin "1") (pinfunction "1_1") (pintype "passive"))
      (node (ref "PS5") (pin "8") (pinfunction "SW_8") (pintype "bidirectional"))
    )
    (net (code "49") (name "Net-(PS5-VCC)") (class "Default")
      (node (ref "C32") (pin "1") (pinfunction "1_1") (pintype "passive"))
      (node (ref "PS5") (pin "6") (pinfunction "VCC_6") (pintype "bidirectional"))
    )
    (net (code "50") (name "Net-(PS6-BOOT)") (class "Default")
      (node (ref "C40") (pin "2") (pinfunction "2_2") (pintype "passive"))
      (node (ref "PS6") (pin "7") (pinfunction "BOOT_7") (pintype "bidirectional"))
    )
    (net (code "51") (name "Net-(PS6-FB)") (class "Default")
      (node (ref "PS6") (pin "5") (pinfunction "FB_5") (pintype "bidirectional"))
      (node (ref "R12") (pin "P$1") (pinfunction "P$1_P$1") (pintype "bidirectional"))
      (node (ref "R13") (pin "P$2") (pinfunction "P$2_P$2") (pintype "bidirectional"))
    )
    (net (code "52") (name "Net-(PS6-SW)") (class "Default")
      (node (ref "C40") (pin "1") (pinfunction "1_1") (pintype "passive"))
      (node (ref "L6") (pin "1") (pinfunction "1_1") (pintype "passive"))
      (node (ref "PS6") (pin "8") (pinfunction "SW_8") (pintype "bidirectional"))
    )
    (net (code "53") (name "Net-(PS6-VCC)") (class "Default")
      (node (ref "C41") (pin "1") (pinfunction "1_1") (pintype "passive"))
      (node (ref "PS6") (pin "6") (pinfunction "VCC_6") (pintype "bidirectional"))
    )
    (net (code "54") (name "Net-(PS7-BOOT)") (class "Default")
      (node (ref "C49") (pin "2") (pinfunction "2_2") (pintype "passive"))
      (node (ref "PS7") (pin "7") (pinfunction "BOOT_7") (pintype "bidirectional"))
    )
    (net (code "55") (name "Net-(PS7-FB)") (class "Default")
      (node (ref "PS7") (pin "5") (pinfunction "FB_5") (pintype "bidirectional"))
      (node (ref "R15") (pin "P$1") (pinfunction "P$1_P$1") (pintype "bidirectional"))
      (node (ref "R16") (pin "P$2") (pinfunction "P$2_P$2") (pintype "bidirectional"))
    )
    (net (code "56") (name "Net-(PS7-SW)") (class "Default")
      (node (ref "C49") (pin "1") (pinfunction "1_1") (pintype "passive"))
      (node (ref "L7") (pin "1") (pinfunction "1_1") (pintype "passive"))
      (node (ref "PS7") (pin "8") (pinfunction "SW_8") (pintype "bidirectional"))
    )
    (net (code "57") (name "Net-(PS7-VCC)") (class "Default")
      (node (ref "C50") (pin "1") (pinfunction "1_1") (pintype "passive"))
      (node (ref "PS7") (pin "6") (pinfunction "VCC_6") (pintype "bidirectional"))
    )
    (net (code "58") (name "Net-(PS8-BOOT)") (class "Default")
      (node (ref "C54") (pin "2") (pinfunction "2_2") (pintype "passive"))
      (node (ref "PS8") (pin "7") (pinfunction "BOOT_7") (pintype "bidirectional"))
    )
    (net (code "59") (name "Net-(PS8-FB)") (class "Default")
      (node (ref "PS8") (pin "5") (pinfunction "FB_5") (pintype "bidirectional"))
      (node (ref "R19") (pin "P$1") (pinfunction "P$1_P$1") (pintype "bidirectional"))
      (node (ref "R20") (pin "P$2") (pinfunction "P$2_P$2") (pintype "bidirectional"))
    )
    (net (code "60") (name "Net-(PS8-SW)") (class "Default")
      (node (ref "C54") (pin "1") (pinfunction "1_1") (pintype "passive"))
      (node (ref "L8") (pin "1") (pinfunction "1_1") (pintype "passive"))
      (node (ref "PS8") (pin "8") (pinfunction "SW_8") (pintype "bidirectional"))
    )
    (net (code "61") (name "Net-(PS8-VCC)") (class "Default")
      (node (ref "C55") (pin "1") (pinfunction "1_1") (pintype "passive"))
      (node (ref "PS8") (pin "6") (pinfunction "VCC_6") (pintype "bidirectional"))
    )
    (net (code "62") (name "Net-(R16-PadP$1)") (class "Default")
      (node (ref "R16") (pin "P$1") (pinfunction "P$1_P$1") (pintype "bidirectional"))
      (node (ref "R2") (pin "P$2") (pinfunction "P$2_P$2") (pintype "bidirectional"))
    )
    (net (code "63") (name "unconnected-(IC3-50MV-Pad4)") (class "Default")
      (node (ref "IC3") (pin "4") (pinfunction "50MV_4") (pintype "bidirectional"))
    )
    (net (code "64") (name "unconnected-(IC3-200MV-Pad6)") (class "Default")
      (node (ref "IC3") (pin "6") (pinfunction "200MV_6") (pintype "bidirectional"))
    )
    (net (code "65") (name "unconnected-(IC3-FB-Pad2)") (class "Default")
      (node (ref "IC3") (pin "2") (pinfunction "FB_2") (pintype "bidirectional"))
    )
    (net (code "66") (name "unconnected-(IC3-SS-Pad11)") (class "Default")
      (node (ref "IC3") (pin "11") (pinfunction "SS_11") (pintype "bidirectional"))
    )
    (net (code "67") (name "unconnected-(IC5-EN-Pad3)") (class "Default")
      (node (ref "IC5") (pin "3") (pinfunction "EN_3") (pintype "bidirectional"))
    )
    (net (code "68") (name "unconnected-(IC7-1.6V-Pad10)") (class "Default")
      (node (ref "IC7") (pin "10") (pinfunction "1.6V_10") (pintype "bidirectional"))
    )
    (net (code "69") (name "unconnected-(IC7-50MV-Pad4)") (class "Default")
      (node (ref "IC7") (pin "4") (pinfunction "50MV_4") (pintype "bidirectional"))
    )
    (net (code "70") (name "unconnected-(IC7-FB-Pad2)") (class "Default")
      (node (ref "IC7") (pin "2") (pinfunction "FB_2") (pintype "bidirectional"))
    )
    (net (code "71") (name "unconnected-(IC7-SS-Pad11)") (class "Default")
      (node (ref "IC7") (pin "11") (pinfunction "SS_11") (pintype "bidirectional"))
    )
    (net (code "72") (name "unconnected-(IC9-1.6V-Pad10)") (class "Default")
      (node (ref "IC9") (pin "10") (pinfunction "1.6V_10") (pintype "bidirectional"))
    )
    (net (code "73") (name "unconnected-(IC9-50MV-Pad4)") (class "Default")
      (node (ref "IC9") (pin "4") (pinfunction "50MV_4") (pintype "bidirectional"))
    )
    (net (code "74") (name "unconnected-(IC9-800MV-Pad9)") (class "Default")
      (node (ref "IC9") (pin "9") (pinfunction "800MV_9") (pintype "bidirectional"))
    )
    (net (code "75") (name "unconnected-(IC9-FB-Pad2)") (class "Default")
      (node (ref "IC9") (pin "2") (pinfunction "FB_2") (pintype "bidirectional"))
    )
    (net (code "76") (name "unconnected-(IC9-SS-Pad11)") (class "Default")
      (node (ref "IC9") (pin "11") (pinfunction "SS_11") (pintype "bidirectional"))
    )
    (net (code "77") (name "unconnected-(IC11-1.6V-Pad10)") (class "Default")
      (node (ref "IC11") (pin "10") (pinfunction "1.6V_10") (pintype "bidirectional"))
    )
    (net (code "78") (name "unconnected-(IC11-50MV-Pad4)") (class "Default")
      (node (ref "IC11") (pin "4") (pinfunction "50MV_4") (pintype "bidirectional"))
    )
    (net (code "79") (name "unconnected-(IC11-100MV-Pad5)") (class "Default")
      (node (ref "IC11") (pin "5") (pinfunction "100MV_5") (pintype "bidirectional"))
    )
    (net (code "80") (name "unconnected-(IC11-FB-Pad2)") (class "Default")
      (node (ref "IC11") (pin "2") (pinfunction "FB_2") (pintype "bidirectional"))
    )
    (net (code "81") (name "unconnected-(IC11-SS-Pad11)") (class "Default")
      (node (ref "IC11") (pin "11") (pinfunction "SS_11") (pintype "bidirectional"))
    )
    (net (code "82") (name "unconnected-(IC12-50MV-Pad4)") (class "Default")
      (node (ref "IC12") (pin "4") (pinfunction "50MV_4") (pintype "bidirectional"))
    )
    (net (code "83") (name "unconnected-(IC12-100MV-Pad5)") (class "Default")
      (node (ref "IC12") (pin "5") (pinfunction "100MV_5") (pintype "bidirectional"))
    )
    (net (code "84") (name "unconnected-(IC12-200MV-Pad6)") (class "Default")
      (node (ref "IC12") (pin "6") (pinfunction "200MV_6") (pintype "bidirectional"))
    )
    (net (code "85") (name "unconnected-(IC12-800MV-Pad9)") (class "Default")
      (node (ref "IC12") (pin "9") (pinfunction "800MV_9") (pintype "bidirectional"))
    )
    (net (code "86") (name "unconnected-(IC12-FB-Pad2)") (class "Default")
      (node (ref "IC12") (pin "2") (pinfunction "FB_2") (pintype "bidirectional"))
    )
    (net (code "87") (name "unconnected-(IC12-SS-Pad11)") (class "Default")
      (node (ref "IC12") (pin "11") (pinfunction "SS_11") (pintype "bidirectional"))
    )
    (net (code "88") (name "unconnected-(IC14-50MV-Pad4)") (class "Default")
      (node (ref "IC14") (pin "4") (pinfunction "50MV_4") (pintype "bidirectional"))
    )
    (net (code "89") (name "unconnected-(IC14-100MV-Pad5)") (class "Default")
      (node (ref "IC14") (pin "5") (pinfunction "100MV_5") (pintype "bidirectional"))
    )
    (net (code "90") (name "unconnected-(IC14-200MV-Pad6)") (class "Default")
      (node (ref "IC14") (pin "6") (pinfunction "200MV_6") (pintype "bidirectional"))
    )
    (net (code "91") (name "unconnected-(IC14-800MV-Pad9)") (class "Default")
      (node (ref "IC14") (pin "9") (pinfunction "800MV_9") (pintype "bidirectional"))
    )
    (net (code "92") (name "unconnected-(IC14-FB-Pad2)") (class "Default")
      (node (ref "IC14") (pin "2") (pinfunction "FB_2") (pintype "bidirectional"))
    )
    (net (code "93") (name "unconnected-(IC14-SS-Pad11)") (class "Default")
      (node (ref "IC14") (pin "11") (pinfunction "SS_11") (pintype "bidirectional"))
    )
    (net (code "94") (name "unconnected-(PS1-PG-Pad4)") (class "Default")
      (node (ref "PS1") (pin "4") (pinfunction "PG_4") (pintype "bidirectional"))
    )
    (net (code "95") (name "unconnected-(PS3-PG-Pad4)") (class "Default")
      (node (ref "PS3") (pin "4") (pinfunction "PG_4") (pintype "bidirectional"))
    )
    (net (code "96") (name "unconnected-(PS4-PG-Pad4)") (class "Default")
      (node (ref "PS4") (pin "4") (pinfunction "PG_4") (pintype "bidirectional"))
    )
    (net (code "97") (name "unconnected-(PS5-PG-Pad4)") (class "Default")
      (node (ref "PS5") (pin "4") (pinfunction "PG_4") (pintype "bidirectional"))
    )
    (net (code "98") (name "unconnected-(PS6-PG-Pad4)") (class "Default")
      (node (ref "PS6") (pin "4") (pinfunction "PG_4") (pintype "bidirectional"))
    )
    (net (code "99") (name "unconnected-(PS7-PG-Pad4)") (class "Default")
      (node (ref "PS7") (pin "4") (pinfunction "PG_4") (pintype "bidirectional"))
    )
    (net (code "100") (name "unconnected-(PS8-PG-Pad4)") (class "Default")
      (node (ref "PS8") (pin "4") (pinfunction "PG_4") (pintype "bidirectional"))
    )
  )
)
